# S7G7_footprint_simplified_w_ethernet_v1p.net
KiCad netlist of a schematic drawn in EAGLE
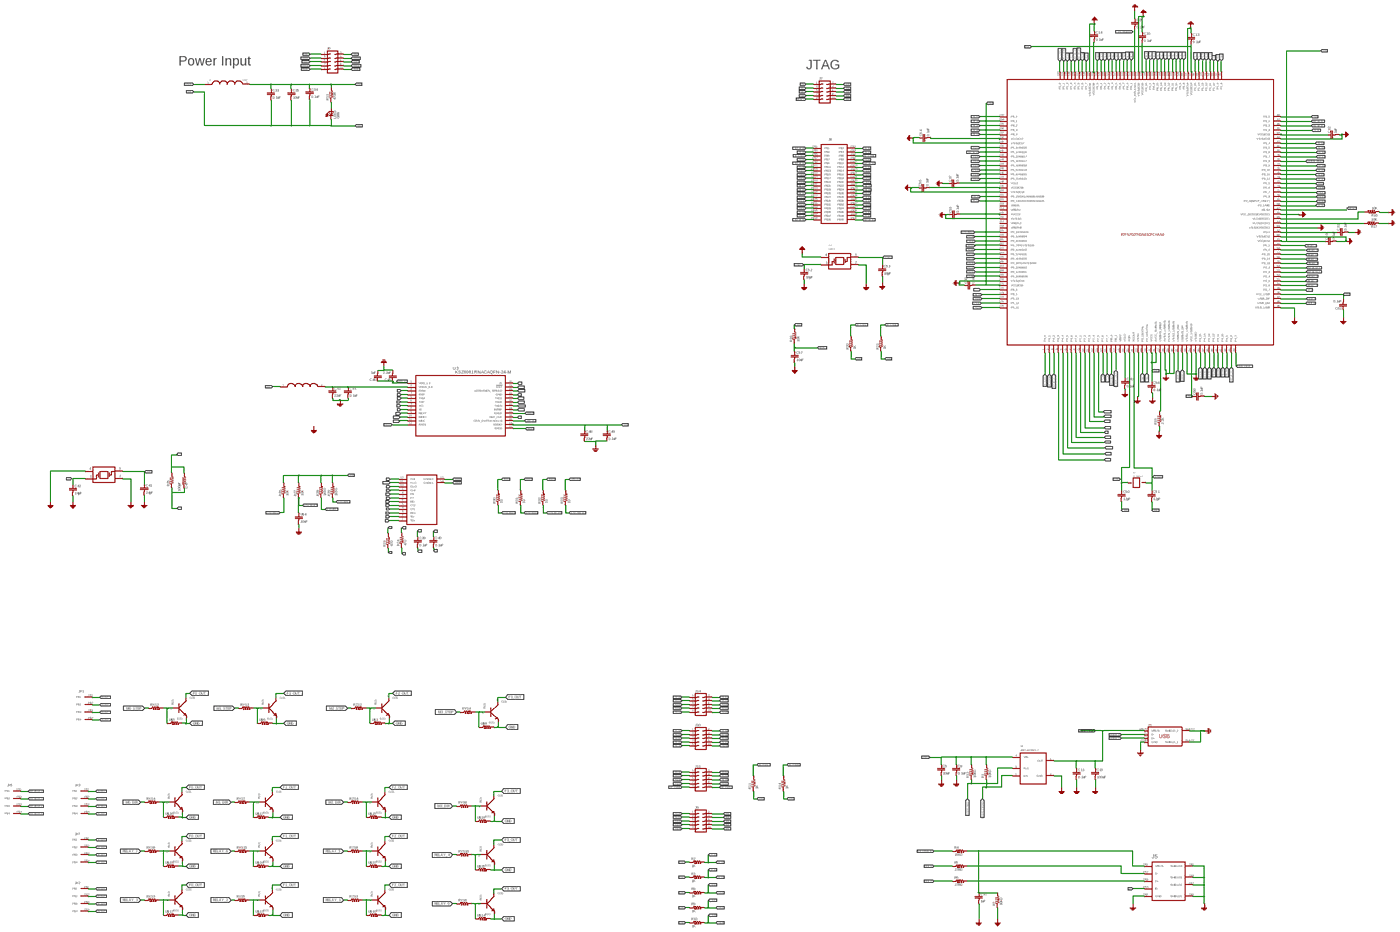
[diagram p0: schematic, sheet 1, overview]
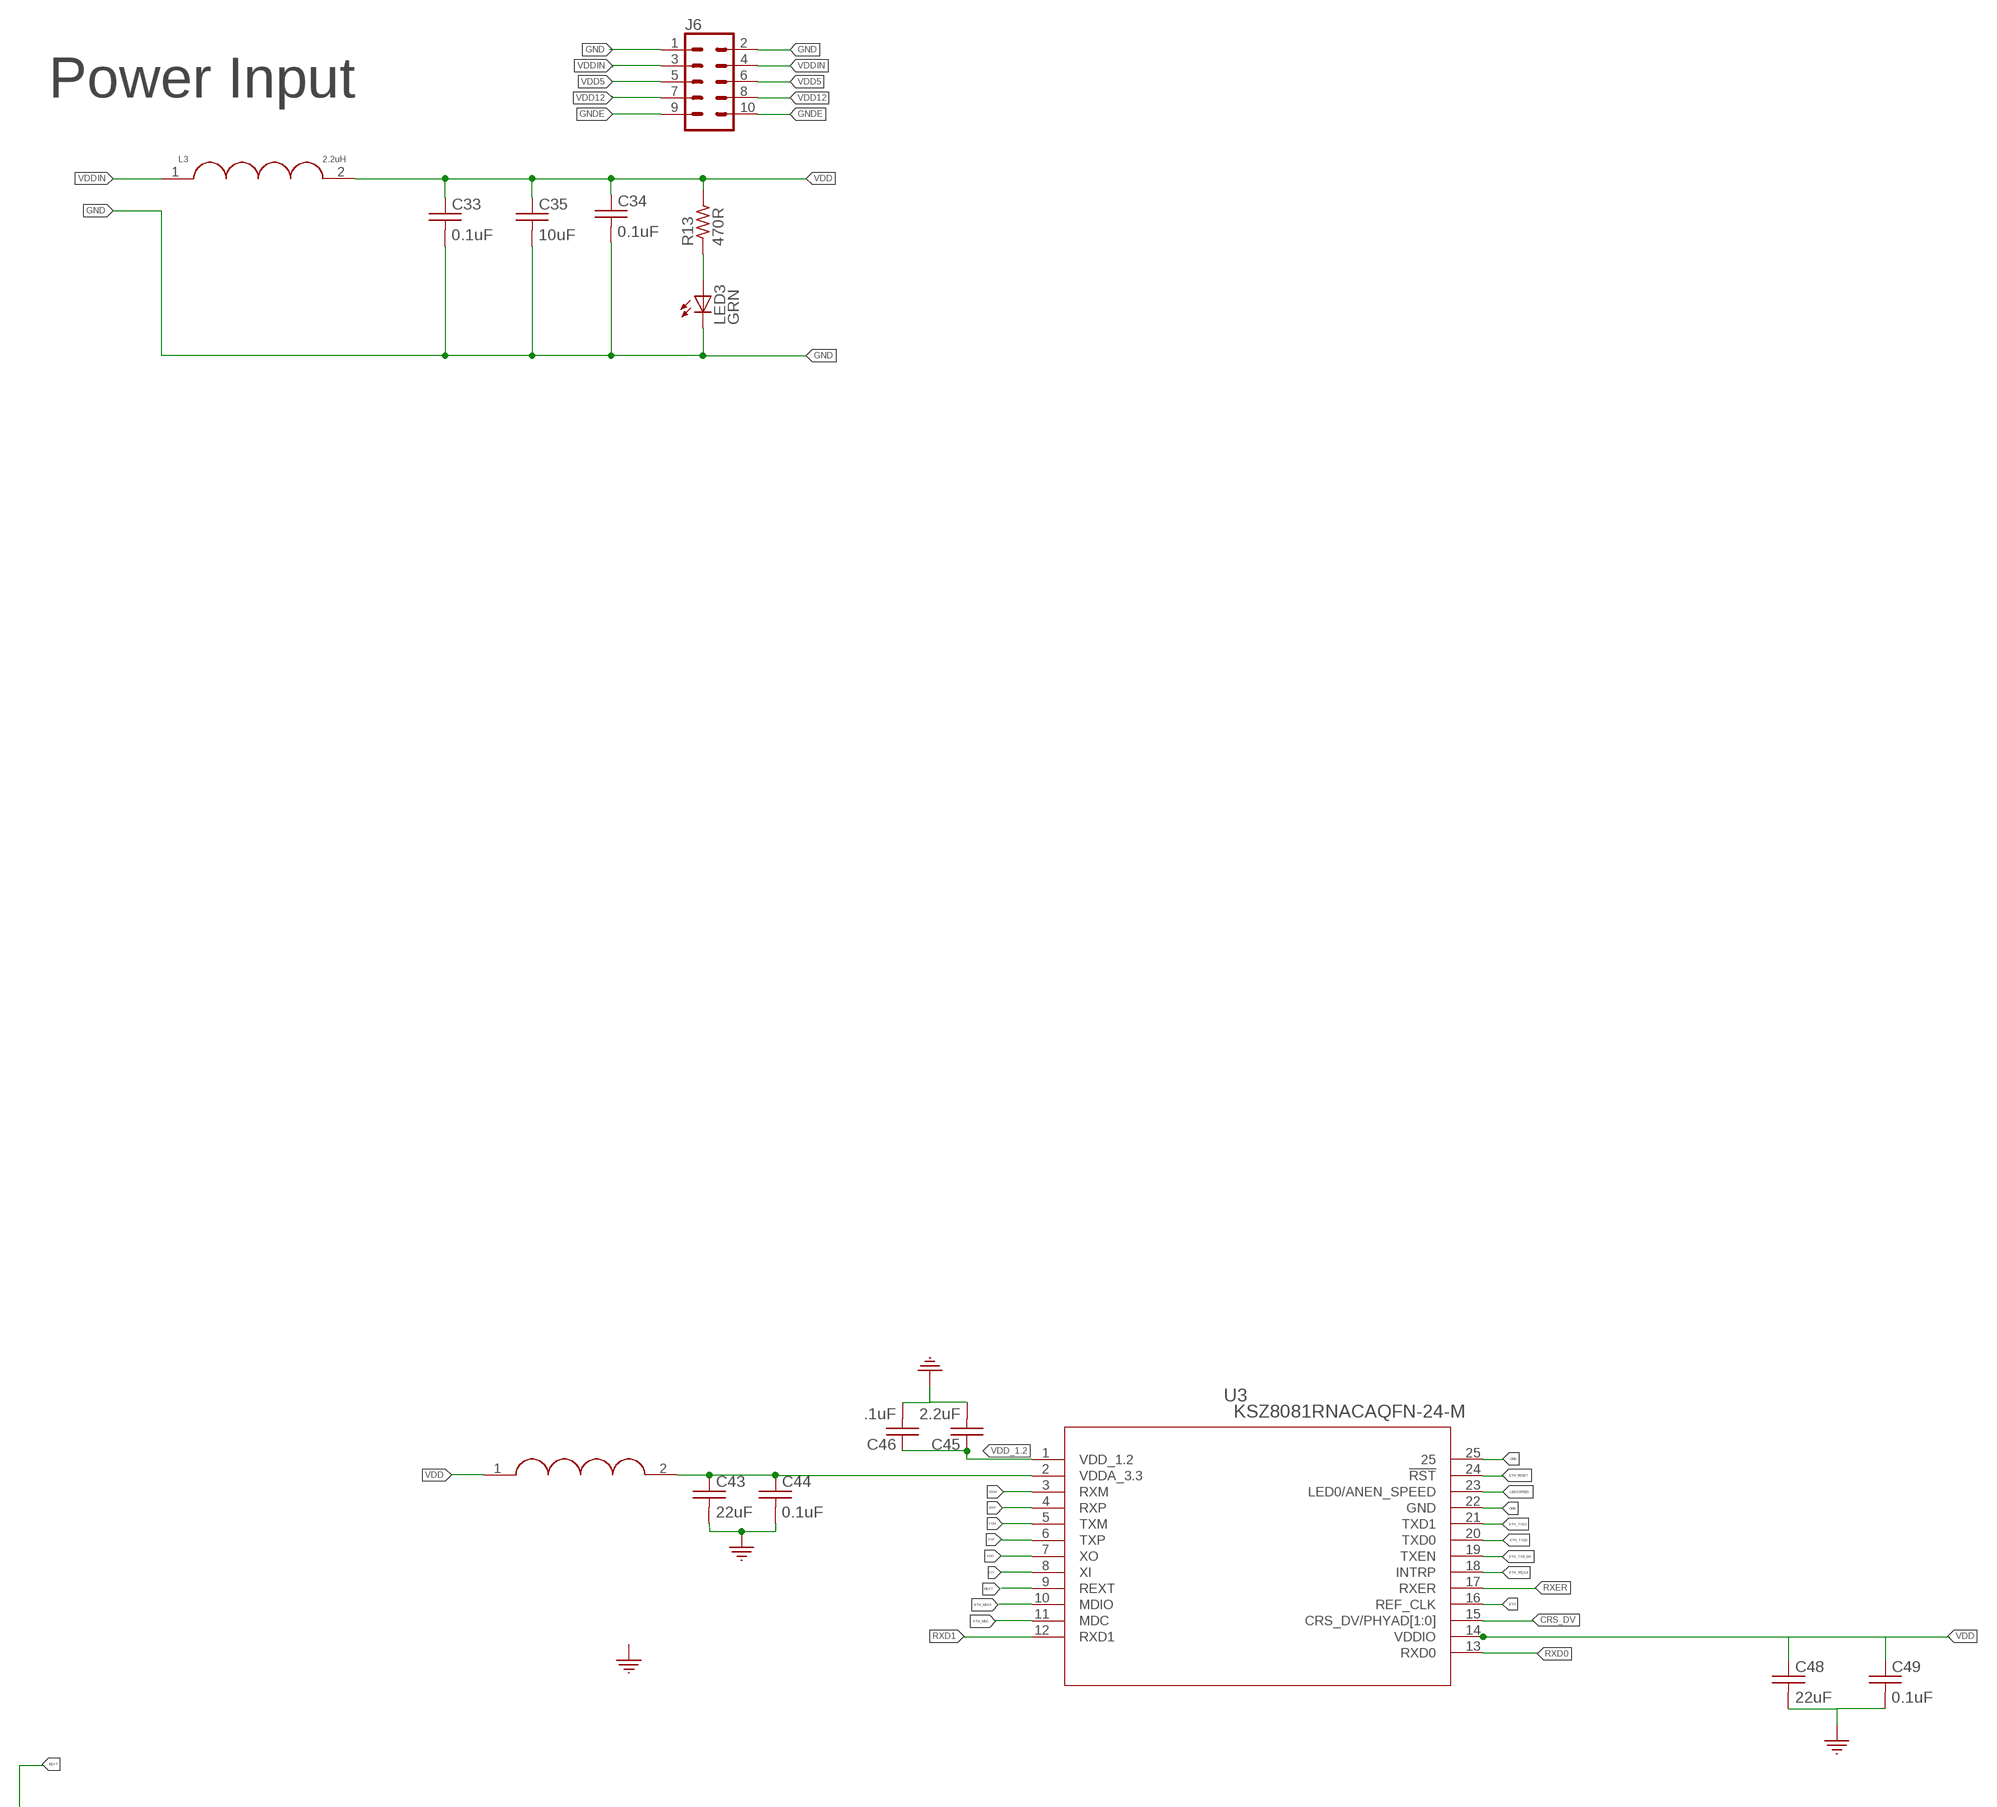
[diagram p1: schematic, sheet 1, part 1 of 4]
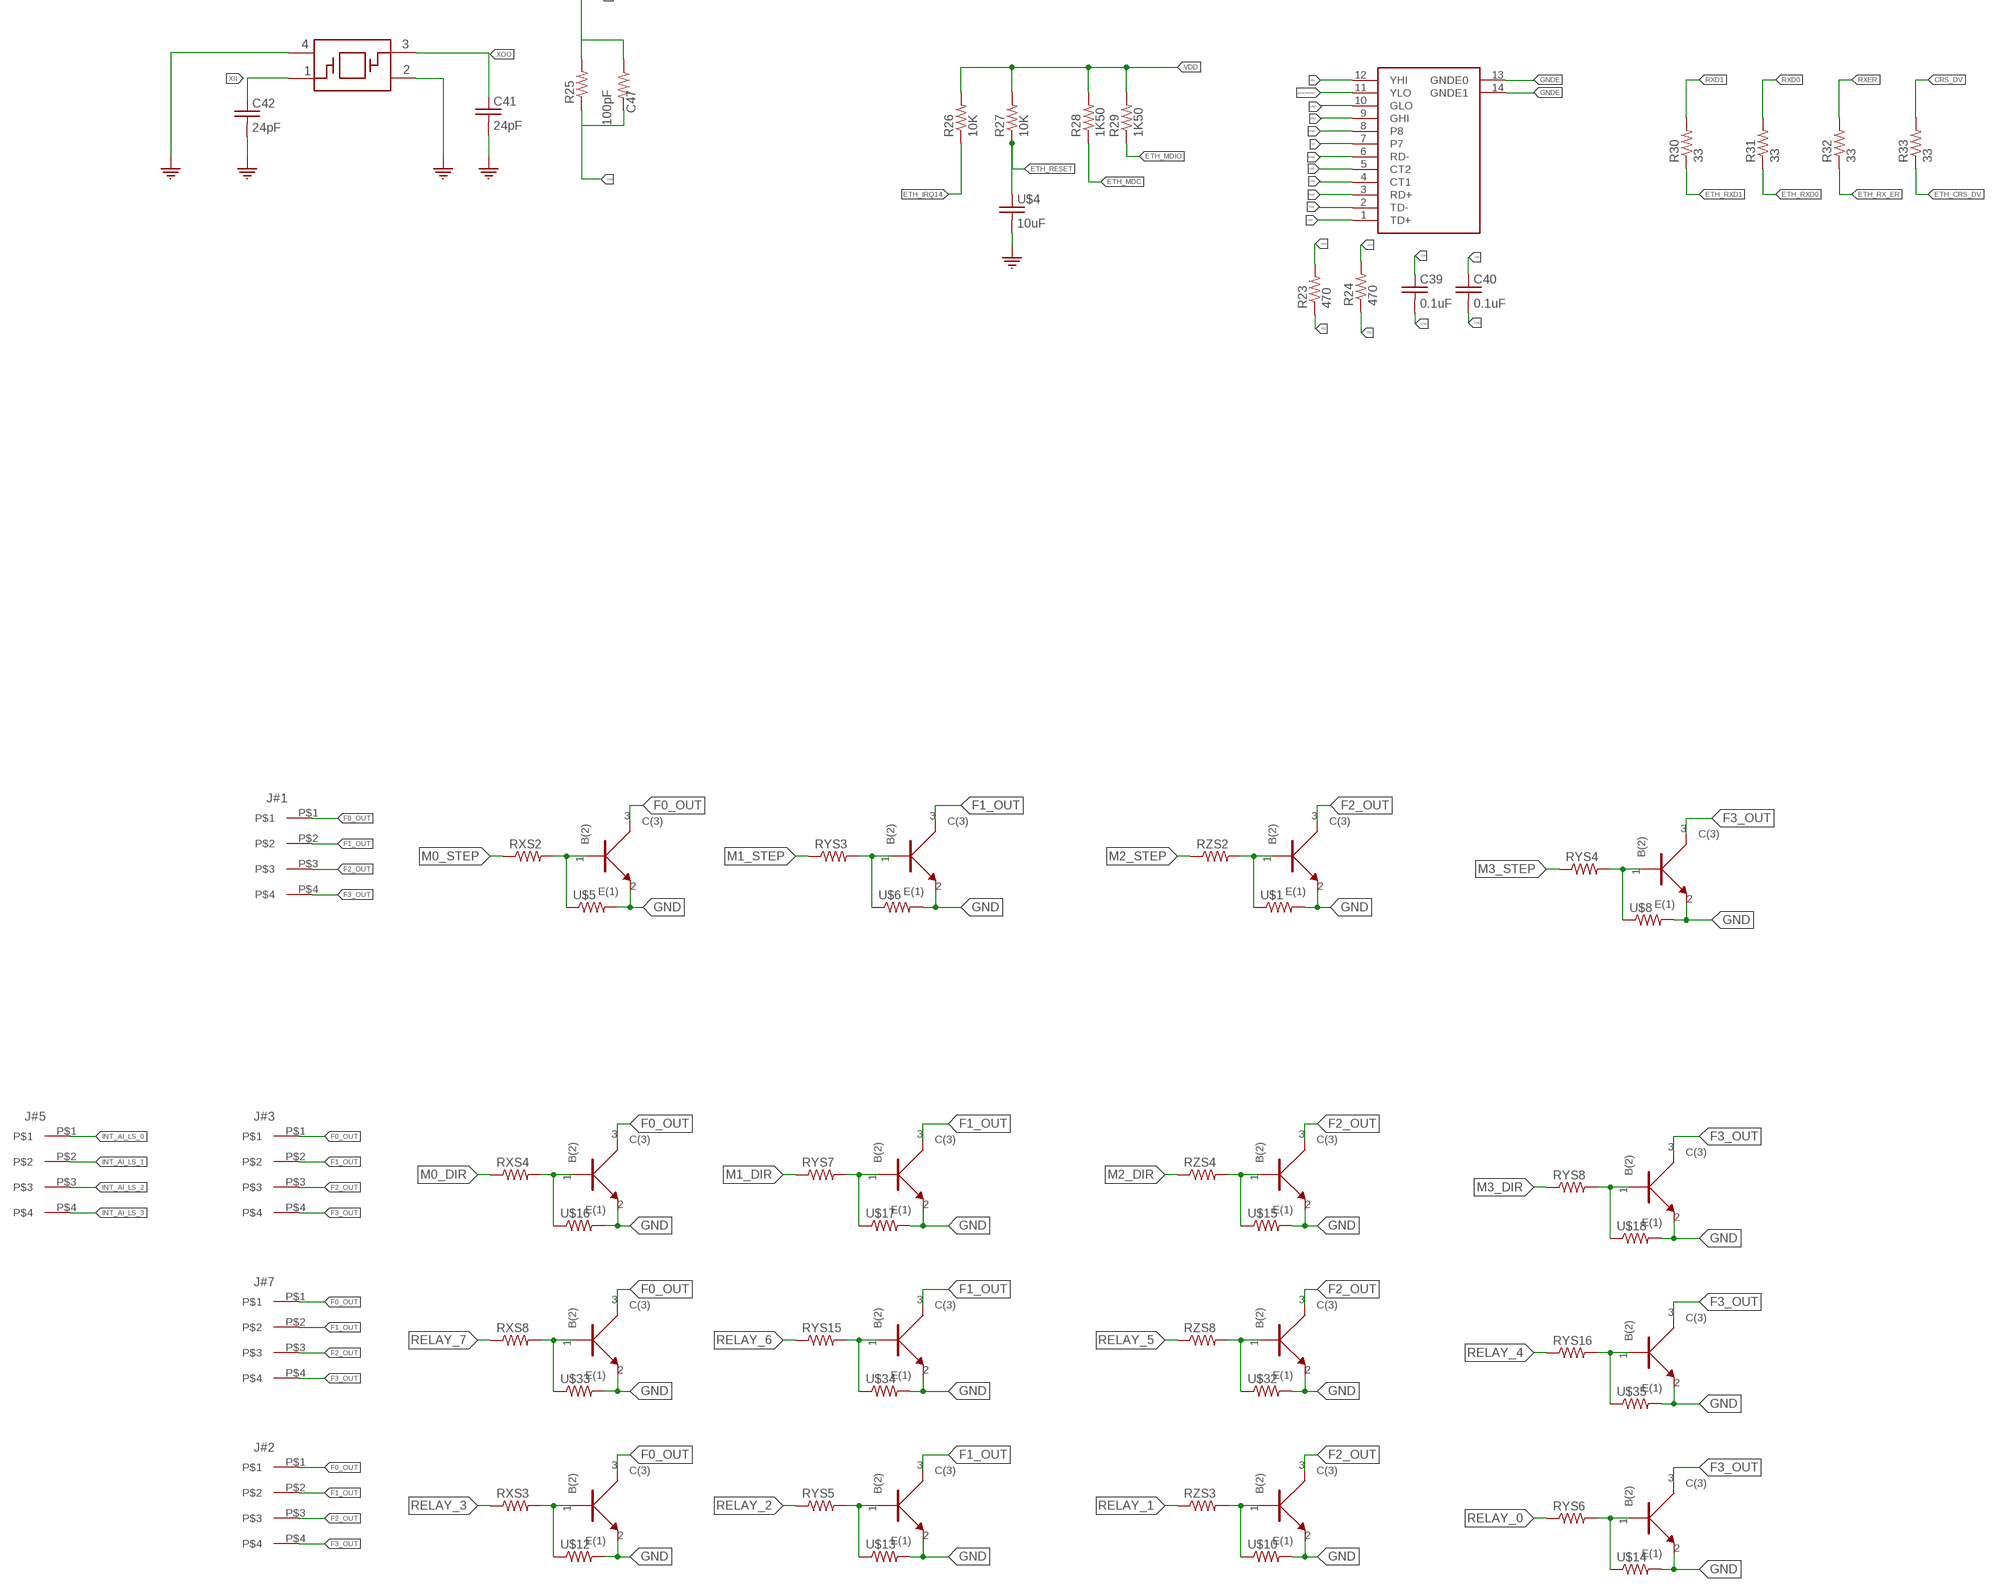
[diagram p2: schematic, sheet 1, part 2 of 4]
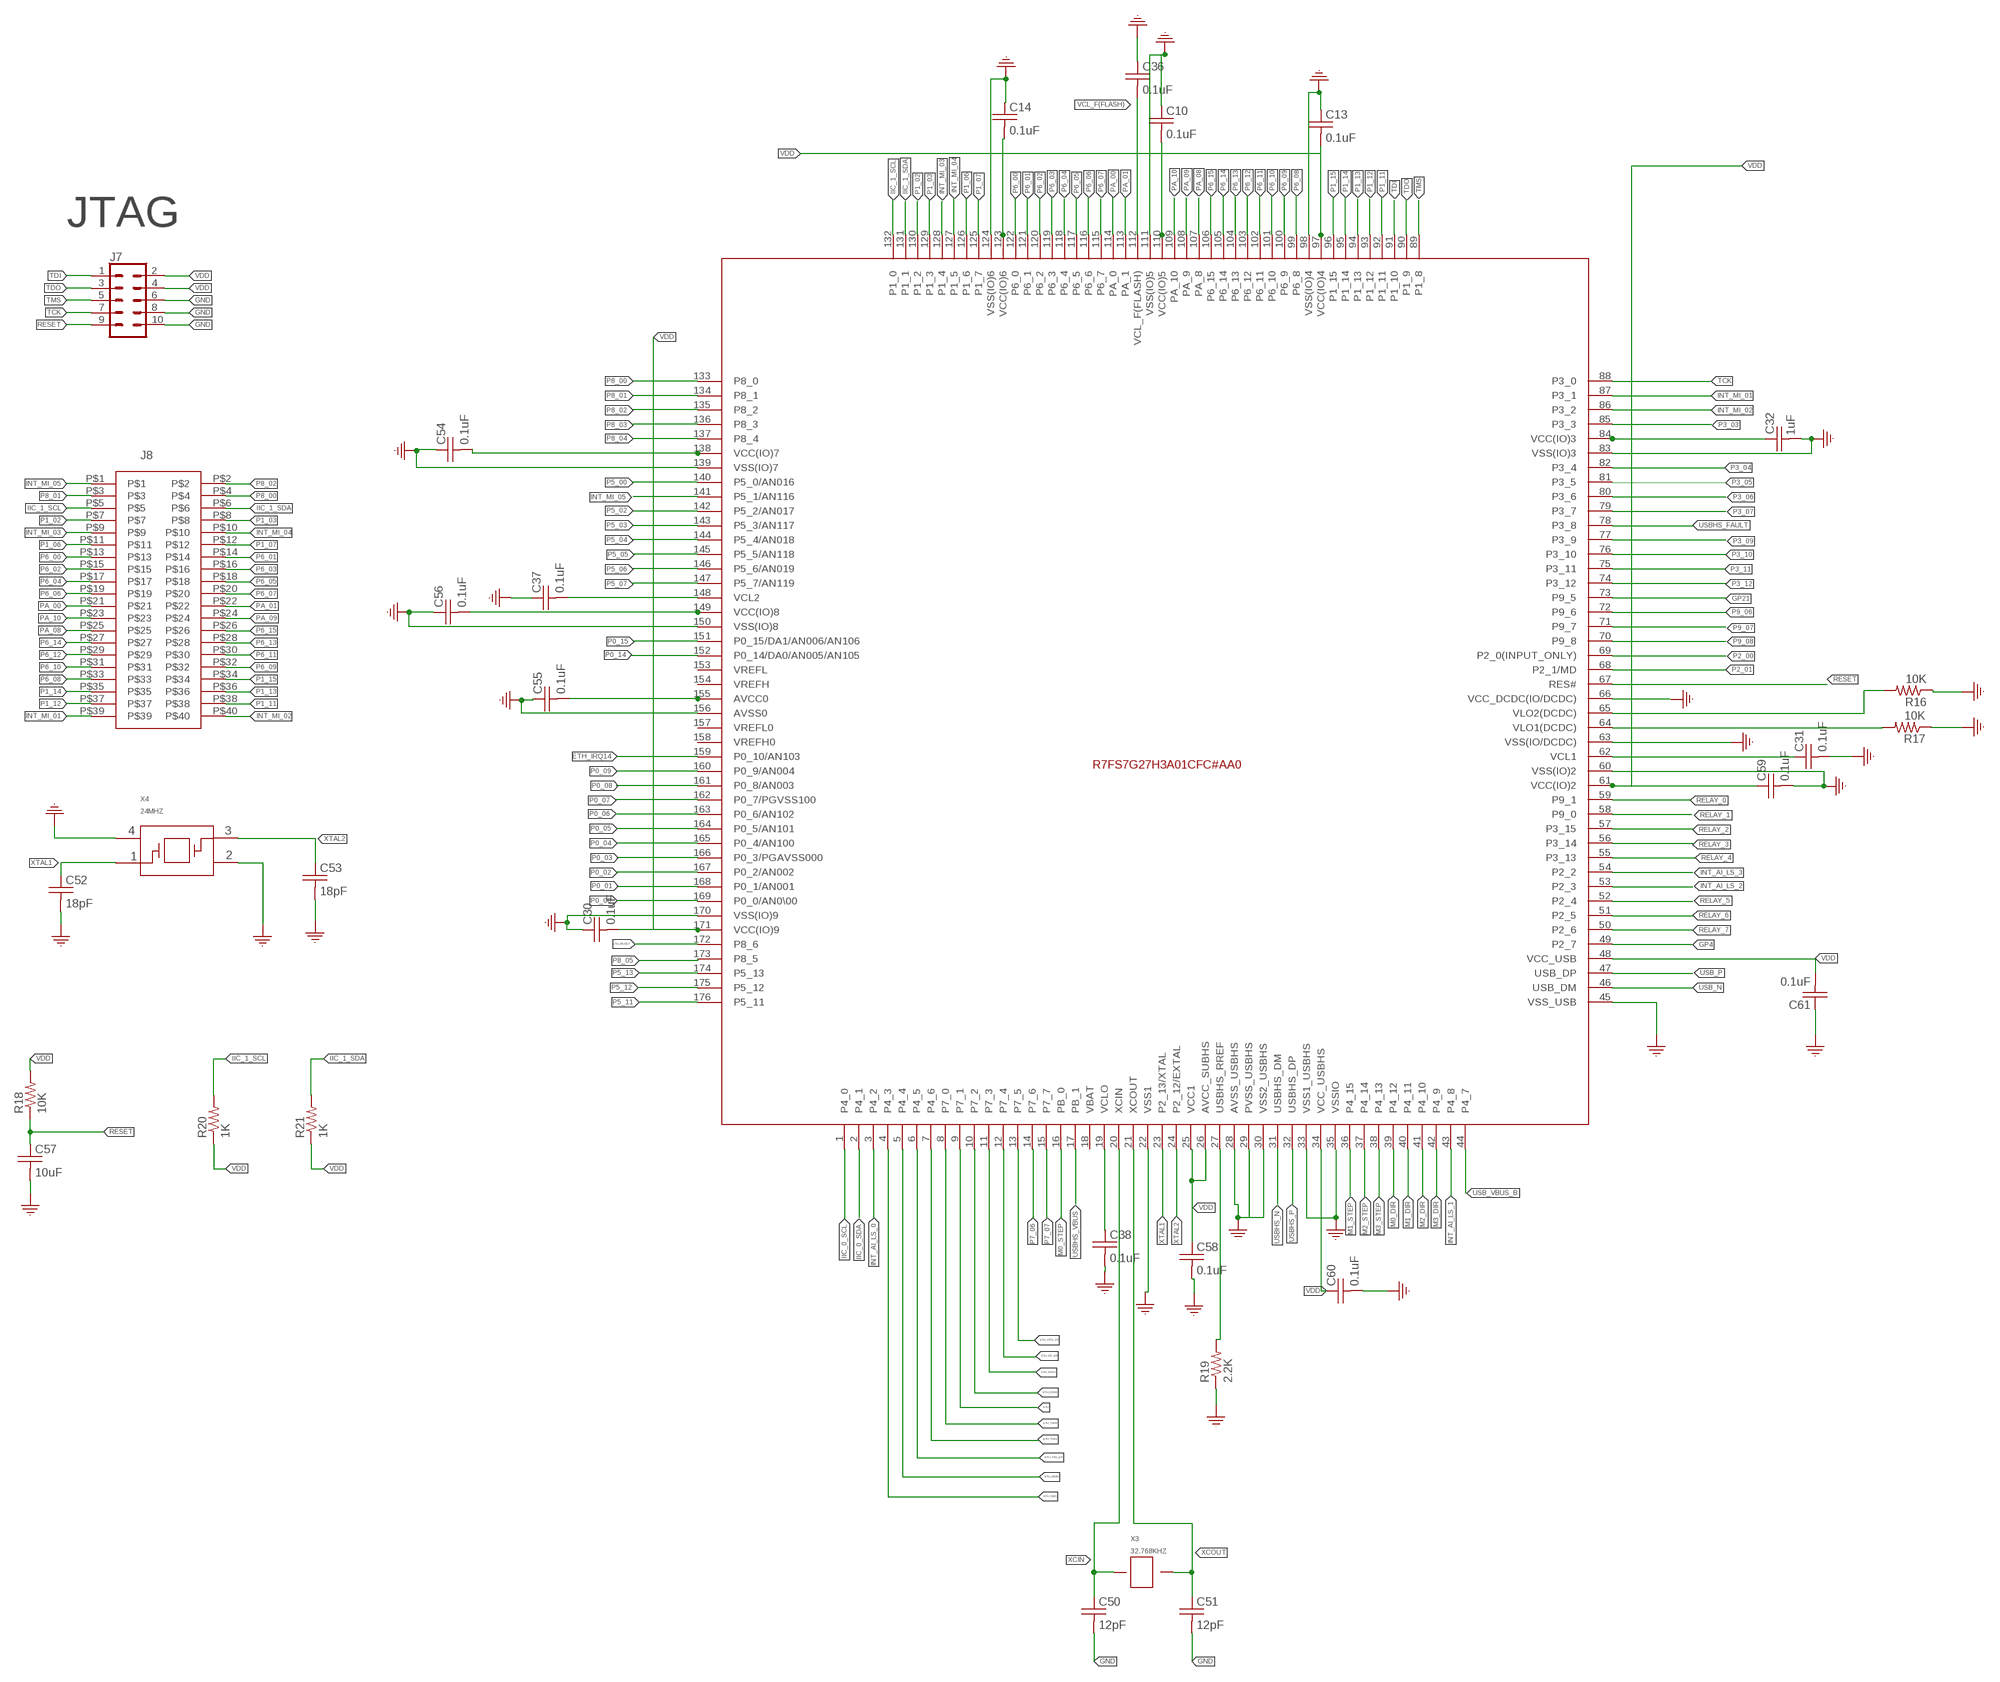
[diagram p3: schematic, sheet 1, part 3 of 4]
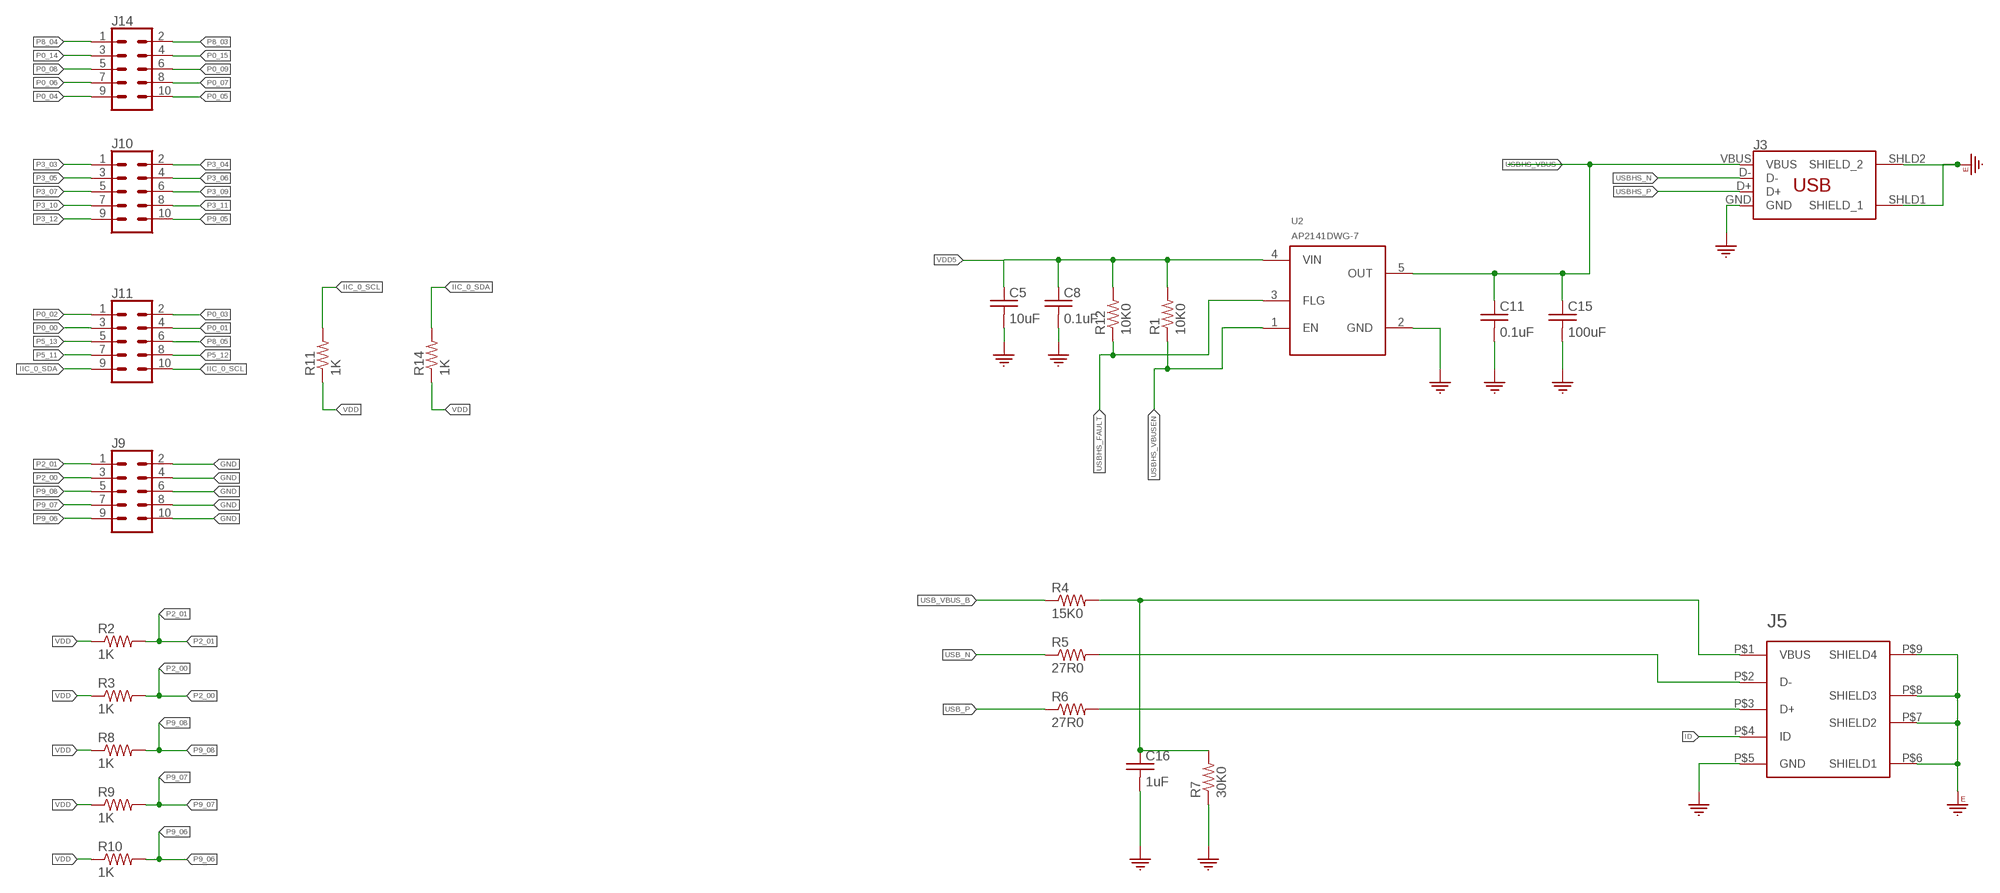
[diagram p4: schematic, sheet 1, part 4 of 4]

(export (version "E")
  (design (tool "Eeschema 10.0.6"))
  (components
    (comp (ref "C5")
      (value "10uF")
      (footprint "eagle-import:0402")
      (libsource (lib "eagle-import") (part "C_0402"))
    )
    (comp (ref "C8")
      (value "0.1uF")
      (footprint "eagle-import:0402")
      (libsource (lib "eagle-import") (part "C_0402"))
    )
    (comp (ref "C10")
      (value "0.1uF")
      (footprint "eagle-import:0402")
      (libsource (lib "eagle-import") (part "C_0402"))
    )
    (comp (ref "C11")
      (value "0.1uF")
      (footprint "eagle-import:0402")
      (libsource (lib "eagle-import") (part "C_0402"))
    )
    (comp (ref "C13")
      (value "0.1uF")
      (footprint "eagle-import:0402")
      (libsource (lib "eagle-import") (part "C_0402"))
    )
    (comp (ref "C14")
      (value "0.1uF")
      (footprint "eagle-import:0402")
      (libsource (lib "eagle-import") (part "C_0402"))
    )
    (comp (ref "C15")
      (value "100uF")
      (footprint "eagle-import:C1210")
      (libsource (lib "eagle-import") (part "C_1210"))
    )
    (comp (ref "C16")
      (value "1uF")
      (footprint "eagle-import:0402")
      (libsource (lib "eagle-import") (part "C_0402"))
    )
    (comp (ref "C30")
      (value "0.1uF")
      (footprint "eagle-import:0402")
      (libsource (lib "eagle-import") (part "C_0402"))
    )
    (comp (ref "C31")
      (value "0.1uF")
      (footprint "eagle-import:0402")
      (libsource (lib "eagle-import") (part "C_0402"))
    )
    (comp (ref "C32")
      (value "1uF")
      (footprint "eagle-import:0402")
      (libsource (lib "eagle-import") (part "C_0402"))
    )
    (comp (ref "C33")
      (value "0.1uF")
      (footprint "eagle-import:0402")
      (libsource (lib "eagle-import") (part "C_0402"))
    )
    (comp (ref "C34")
      (value "0.1uF")
      (footprint "eagle-import:0402")
      (libsource (lib "eagle-import") (part "C_0402"))
    )
    (comp (ref "C35")
      (value "10uF")
      (footprint "eagle-import:0402")
      (libsource (lib "eagle-import") (part "C_0402"))
    )
    (comp (ref "C36")
      (value "0.1uF")
      (footprint "eagle-import:0402")
      (libsource (lib "eagle-import") (part "C_0402"))
    )
    (comp (ref "C37")
      (value "0.1uF")
      (footprint "eagle-import:0402")
      (libsource (lib "eagle-import") (part "C_0402"))
    )
    (comp (ref "C38")
      (value "0.1uF")
      (footprint "eagle-import:0402")
      (libsource (lib "eagle-import") (part "C_0402"))
    )
    (comp (ref "C39")
      (value "0.1uF")
      (footprint "eagle-import:0402")
      (libsource (lib "eagle-import") (part "C_0402"))
    )
    (comp (ref "C40")
      (value "0.1uF")
      (footprint "eagle-import:0402")
      (libsource (lib "eagle-import") (part "C_0402"))
    )
    (comp (ref "C41")
      (value "24pF")
      (footprint "eagle-import:0402")
      (libsource (lib "eagle-import") (part "C_0402"))
    )
    (comp (ref "C42")
      (value "24pF")
      (footprint "eagle-import:0402")
      (libsource (lib "eagle-import") (part "C_0402"))
    )
    (comp (ref "C43")
      (value "22uF")
      (footprint "eagle-import:0603")
      (libsource (lib "eagle-import") (part "C_0603"))
    )
    (comp (ref "C44")
      (value "0.1uF")
      (footprint "eagle-import:0402")
      (libsource (lib "eagle-import") (part "C_0402"))
    )
    (comp (ref "C45")
      (value "2.2uF")
      (footprint "eagle-import:0402")
      (libsource (lib "eagle-import") (part "C_0402"))
    )
    (comp (ref "C46")
      (value ".1uF")
      (footprint "eagle-import:0402")
      (libsource (lib "eagle-import") (part "C_0402"))
    )
    (comp (ref "C47")
      (value "100pF")
      (footprint "eagle-import:0402")
      (libsource (lib "eagle-import") (part "R_0402"))
    )
    (comp (ref "C48")
      (value "22uF")
      (footprint "eagle-import:0603")
      (libsource (lib "eagle-import") (part "C_0603"))
    )
    (comp (ref "C49")
      (value "0.1uF")
      (footprint "eagle-import:0402")
      (libsource (lib "eagle-import") (part "C_0402"))
    )
    (comp (ref "C50")
      (value "12pF")
      (footprint "eagle-import:0402")
      (libsource (lib "eagle-import") (part "C_0402"))
    )
    (comp (ref "C51")
      (value "12pF")
      (footprint "eagle-import:0402")
      (libsource (lib "eagle-import") (part "C_0402"))
    )
    (comp (ref "C52")
      (value "18pF")
      (footprint "eagle-import:0402")
      (libsource (lib "eagle-import") (part "C_0402"))
    )
    (comp (ref "C53")
      (value "18pF")
      (footprint "eagle-import:0402")
      (libsource (lib "eagle-import") (part "C_0402"))
    )
    (comp (ref "C54")
      (value "0.1uF")
      (footprint "eagle-import:0402")
      (libsource (lib "eagle-import") (part "C_0402"))
    )
    (comp (ref "C55")
      (value "0.1uF")
      (footprint "eagle-import:0402")
      (libsource (lib "eagle-import") (part "C_0402"))
    )
    (comp (ref "C56")
      (value "0.1uF")
      (footprint "eagle-import:0402")
      (libsource (lib "eagle-import") (part "C_0402"))
    )
    (comp (ref "C57")
      (value "10uF")
      (footprint "eagle-import:0402")
      (libsource (lib "eagle-import") (part "C_0402"))
    )
    (comp (ref "C58")
      (value "0.1uF")
      (footprint "eagle-import:0402")
      (libsource (lib "eagle-import") (part "C_0402"))
    )
    (comp (ref "C59")
      (value "0.1uF")
      (footprint "eagle-import:0402")
      (libsource (lib "eagle-import") (part "C_0402"))
    )
    (comp (ref "C60")
      (value "0.1uF")
      (footprint "eagle-import:0402")
      (libsource (lib "eagle-import") (part "C_0402"))
    )
    (comp (ref "C61")
      (value "0.1uF")
      (footprint "eagle-import:0402")
      (libsource (lib "eagle-import") (part "C_0402"))
    )
    (comp (ref "FB2/2")
      (value "FB_0805_120_OHM")
      (footprint "eagle-import:0805")
      (libsource (lib "eagle-import") (part "FB_0805_120_OHM"))
    )
    (comp (ref "J#1")
      (value "3.81MM_1_X_4_RT_ANGLE_PLUG_HEADER")
      (footprint "eagle-import:1X4_3.81MM_PITCH")
      (libsource (lib "eagle-import") (part "3.81MM_1_X_4_RT_ANGLE_PLUG_HEADER"))
    )
    (comp (ref "J#2")
      (value "3.81MM_1_X_4_RT_ANGLE_PLUG_HEADER")
      (footprint "eagle-import:1X4_3.81MM_PITCH")
      (libsource (lib "eagle-import") (part "3.81MM_1_X_4_RT_ANGLE_PLUG_HEADER"))
    )
    (comp (ref "J#3")
      (value "3.81MM_1_X_4_RT_ANGLE_PLUG_HEADER")
      (footprint "eagle-import:1X4_3.81MM_PITCH")
      (libsource (lib "eagle-import") (part "3.81MM_1_X_4_RT_ANGLE_PLUG_HEADER"))
    )
    (comp (ref "J#5")
      (value "3.81MM_1_X_4_RT_ANGLE_PLUG_HEADER")
      (footprint "eagle-import:1X4_3.81MM_PITCH")
      (libsource (lib "eagle-import") (part "3.81MM_1_X_4_RT_ANGLE_PLUG_HEADER"))
    )
    (comp (ref "J#7")
      (value "3.81MM_1_X_4_RT_ANGLE_PLUG_HEADER")
      (footprint "eagle-import:1X4_3.81MM_PITCH")
      (libsource (lib "eagle-import") (part "3.81MM_1_X_4_RT_ANGLE_PLUG_HEADER"))
    )
    (comp (ref "J3")
      (value "USB_A")
      (footprint "eagle-import:USB_A_SMT")
      (libsource (lib "eagle-import") (part "USB_A"))
    )
    (comp (ref "J5")
      (value "USB_MICRO-B")
      (footprint "eagle-import:USB_MICRO-B")
      (libsource (lib "eagle-import") (part "USB_MICRO-B"))
    )
    (comp (ref "J6")
      (value "CONN_05X2PTH")
      (footprint "eagle-import:2X5")
      (libsource (lib "eagle-import") (part "CONN_05X2PTH"))
    )
    (comp (ref "J7")
      (value "CONN_05X2PTH")
      (footprint "eagle-import:2X5")
      (libsource (lib "eagle-import") (part "CONN_05X2PTH"))
    )
    (comp (ref "J8")
      (value "HEADER_2_X_20_GENERIC")
      (footprint "eagle-import:HEADER_2_X_20_.1_INCH")
      (libsource (lib "eagle-import") (part "HEADER_2_X_20_GENERIC"))
    )
    (comp (ref "J9")
      (value "CONN_05X2SHD_SMD")
      (footprint "eagle-import:2X5-SHROUDED_SMD")
      (libsource (lib "eagle-import") (part "CONN_05X2SHD_SMD"))
    )
    (comp (ref "J10")
      (value "CONN_05X2NO_SILK")
      (footprint "eagle-import:2X5_NOSILK")
      (libsource (lib "eagle-import") (part "CONN_05X2NO_SILK"))
    )
    (comp (ref "J11")
      (value "CONN_05X2NO_SILK")
      (footprint "eagle-import:2X5_NOSILK")
      (libsource (lib "eagle-import") (part "CONN_05X2NO_SILK"))
    )
    (comp (ref "J14")
      (value "CONN_05X2NO_SILK")
      (footprint "eagle-import:2X5_NOSILK")
      (libsource (lib "eagle-import") (part "CONN_05X2NO_SILK"))
    )
    (comp (ref "L3")
      (value "2.2uH")
      (footprint "eagle-import:1008_(2520_METRIC)")
      (libsource (lib "eagle-import") (part "INDUCTOR_1008_2.2_MH_1.3A"))
    )
    (comp (ref "LED3")
      (value "LED_0805_GREEN")
      (footprint "eagle-import:LED_0805_GREEN")
      (libsource (lib "eagle-import") (part "LED_0805_GREEN"))
    )
    (comp (ref "R1")
      (value "10K0")
      (footprint "eagle-import:0402")
      (libsource (lib "eagle-import") (part "R_0402"))
    )
    (comp (ref "R2")
      (value "1K")
      (footprint "eagle-import:0402")
      (libsource (lib "eagle-import") (part "R_0402"))
    )
    (comp (ref "R3")
      (value "1K")
      (footprint "eagle-import:0402")
      (libsource (lib "eagle-import") (part "R_0402"))
    )
    (comp (ref "R4")
      (value "15K0")
      (footprint "eagle-import:0402")
      (libsource (lib "eagle-import") (part "R_0402"))
    )
    (comp (ref "R5")
      (value "27R0")
      (footprint "eagle-import:0402")
      (libsource (lib "eagle-import") (part "R_0402"))
    )
    (comp (ref "R6")
      (value "27R0")
      (footprint "eagle-import:0402")
      (libsource (lib "eagle-import") (part "R_0402"))
    )
    (comp (ref "R7")
      (value "30K0")
      (footprint "eagle-import:0402")
      (libsource (lib "eagle-import") (part "R_0402"))
    )
    (comp (ref "R8")
      (value "1K")
      (footprint "eagle-import:0402")
      (libsource (lib "eagle-import") (part "R_0402"))
    )
    (comp (ref "R9")
      (value "1K")
      (footprint "eagle-import:0402")
      (libsource (lib "eagle-import") (part "R_0402"))
    )
    (comp (ref "R10")
      (value "1K")
      (footprint "eagle-import:0402")
      (libsource (lib "eagle-import") (part "R_0402"))
    )
    (comp (ref "R11")
      (value "1K")
      (footprint "eagle-import:0402")
      (libsource (lib "eagle-import") (part "R_0402"))
    )
    (comp (ref "R12")
      (value "10K0")
      (footprint "eagle-import:0402")
      (libsource (lib "eagle-import") (part "R_0402"))
    )
    (comp (ref "R13")
      (value "470R")
      (footprint "eagle-import:0402")
      (libsource (lib "eagle-import") (part "R_0402"))
    )
    (comp (ref "R14")
      (value "1K")
      (footprint "eagle-import:0402")
      (libsource (lib "eagle-import") (part "R_0402"))
    )
    (comp (ref "R16")
      (value "10K")
      (footprint "eagle-import:0402")
      (libsource (lib "eagle-import") (part "R_0402"))
    )
    (comp (ref "R17")
      (value "10K")
      (footprint "eagle-import:0402")
      (libsource (lib "eagle-import") (part "R_0402"))
    )
    (comp (ref "R18")
      (value "10K")
      (footprint "eagle-import:0402")
      (libsource (lib "eagle-import") (part "R_0402"))
    )
    (comp (ref "R19")
      (value "2.2K")
      (footprint "eagle-import:0402")
      (libsource (lib "eagle-import") (part "R_0402"))
    )
    (comp (ref "R20")
      (value "1K")
      (footprint "eagle-import:0402")
      (libsource (lib "eagle-import") (part "R_0402"))
    )
    (comp (ref "R21")
      (value "1K")
      (footprint "eagle-import:0402")
      (libsource (lib "eagle-import") (part "R_0402"))
    )
    (comp (ref "R23")
      (value "470")
      (footprint "eagle-import:0402")
      (libsource (lib "eagle-import") (part "R_0402"))
    )
    (comp (ref "R24")
      (value "470")
      (footprint "eagle-import:0402")
      (libsource (lib "eagle-import") (part "R_0402"))
    )
    (comp (ref "R25")
      (value "6k49")
      (footprint "eagle-import:0402")
      (libsource (lib "eagle-import") (part "R_0402"))
    )
    (comp (ref "R26")
      (value "10K")
      (footprint "eagle-import:0402")
      (libsource (lib "eagle-import") (part "R_0402"))
    )
    (comp (ref "R27")
      (value "10K")
      (footprint "eagle-import:0402")
      (libsource (lib "eagle-import") (part "R_0402"))
    )
    (comp (ref "R28")
      (value "1K50")
      (footprint "eagle-import:0402")
      (libsource (lib "eagle-import") (part "R_0402"))
    )
    (comp (ref "R29")
      (value "1K50")
      (footprint "eagle-import:0402")
      (libsource (lib "eagle-import") (part "R_0402"))
    )
    (comp (ref "R30")
      (value "33")
      (footprint "eagle-import:0402")
      (libsource (lib "eagle-import") (part "R_0402"))
    )
    (comp (ref "R31")
      (value "33")
      (footprint "eagle-import:0402")
      (libsource (lib "eagle-import") (part "R_0402"))
    )
    (comp (ref "R32")
      (value "33")
      (footprint "eagle-import:0402")
      (libsource (lib "eagle-import") (part "R_0402"))
    )
    (comp (ref "R33")
      (value "33")
      (footprint "eagle-import:0402")
      (libsource (lib "eagle-import") (part "R_0402"))
    )
    (comp (ref "RXS2")
      (value "R_0402")
      (footprint "eagle-import:0402")
      (libsource (lib "eagle-import") (part "R_0402"))
    )
    (comp (ref "RXS3")
      (value "R_0402")
      (footprint "eagle-import:0402")
      (libsource (lib "eagle-import") (part "R_0402"))
    )
    (comp (ref "RXS4")
      (value "R_0402")
      (footprint "eagle-import:0402")
      (libsource (lib "eagle-import") (part "R_0402"))
    )
    (comp (ref "RXS8")
      (value "R_0402")
      (footprint "eagle-import:0402")
      (libsource (lib "eagle-import") (part "R_0402"))
    )
    (comp (ref "RYS3")
      (value "R_0402")
      (footprint "eagle-import:0402")
      (libsource (lib "eagle-import") (part "R_0402"))
    )
    (comp (ref "RYS4")
      (value "R_0402")
      (footprint "eagle-import:0402")
      (libsource (lib "eagle-import") (part "R_0402"))
    )
    (comp (ref "RYS5")
      (value "R_0402")
      (footprint "eagle-import:0402")
      (libsource (lib "eagle-import") (part "R_0402"))
    )
    (comp (ref "RYS6")
      (value "R_0402")
      (footprint "eagle-import:0402")
      (libsource (lib "eagle-import") (part "R_0402"))
    )
    (comp (ref "RYS7")
      (value "R_0402")
      (footprint "eagle-import:0402")
      (libsource (lib "eagle-import") (part "R_0402"))
    )
    (comp (ref "RYS8")
      (value "R_0402")
      (footprint "eagle-import:0402")
      (libsource (lib "eagle-import") (part "R_0402"))
    )
    (comp (ref "RYS15")
      (value "R_0402")
      (footprint "eagle-import:0402")
      (libsource (lib "eagle-import") (part "R_0402"))
    )
    (comp (ref "RYS16")
      (value "R_0402")
      (footprint "eagle-import:0402")
      (libsource (lib "eagle-import") (part "R_0402"))
    )
    (comp (ref "RZS2")
      (value "R_0402")
      (footprint "eagle-import:0402")
      (libsource (lib "eagle-import") (part "R_0402"))
    )
    (comp (ref "RZS3")
      (value "R_0402")
      (footprint "eagle-import:0402")
      (libsource (lib "eagle-import") (part "R_0402"))
    )
    (comp (ref "RZS4")
      (value "R_0402")
      (footprint "eagle-import:0402")
      (libsource (lib "eagle-import") (part "R_0402"))
    )
    (comp (ref "RZS8")
      (value "R_0402")
      (footprint "eagle-import:0402")
      (libsource (lib "eagle-import") (part "R_0402"))
    )
    (comp (ref "U$1")
      (value "R_0402")
      (footprint "eagle-import:0402")
      (libsource (lib "eagle-import") (part "R_0402"))
    )
    (comp (ref "U$2")
      (value "RJ45_WITH_ELEC")
      (footprint "eagle-import:RJ45_TH_ELEC")
      (libsource (lib "eagle-import") (part "RJ45_WITH_ELEC"))
    )
    (comp (ref "U$3")
      (value "XTAL_25_MHZ")
      (footprint "eagle-import:SMD_3225")
      (libsource (lib "eagle-import") (part "XTAL_25_MHZ"))
    )
    (comp (ref "U$4")
      (value "10uF")
      (footprint "eagle-import:0402")
      (libsource (lib "eagle-import") (part "C_0402"))
    )
    (comp (ref "U$5")
      (value "R_0402")
      (footprint "eagle-import:0402")
      (libsource (lib "eagle-import") (part "R_0402"))
    )
    (comp (ref "U$6")
      (value "R_0402")
      (footprint "eagle-import:0402")
      (libsource (lib "eagle-import") (part "R_0402"))
    )
    (comp (ref "U$8")
      (value "R_0402")
      (footprint "eagle-import:0402")
      (libsource (lib "eagle-import") (part "R_0402"))
    )
    (comp (ref "U$10")
      (value "R_0402")
      (footprint "eagle-import:0402")
      (libsource (lib "eagle-import") (part "R_0402"))
    )
    (comp (ref "U$12")
      (value "R_0402")
      (footprint "eagle-import:0402")
      (libsource (lib "eagle-import") (part "R_0402"))
    )
    (comp (ref "U$13")
      (value "R_0402")
      (footprint "eagle-import:0402")
      (libsource (lib "eagle-import") (part "R_0402"))
    )
    (comp (ref "U$14")
      (value "R_0402")
      (footprint "eagle-import:0402")
      (libsource (lib "eagle-import") (part "R_0402"))
    )
    (comp (ref "U$15")
      (value "R_0402")
      (footprint "eagle-import:0402")
      (libsource (lib "eagle-import") (part "R_0402"))
    )
    (comp (ref "U$16")
      (value "R_0402")
      (footprint "eagle-import:0402")
      (libsource (lib "eagle-import") (part "R_0402"))
    )
    (comp (ref "U$17")
      (value "R_0402")
      (footprint "eagle-import:0402")
      (libsource (lib "eagle-import") (part "R_0402"))
    )
    (comp (ref "U$18")
      (value "R_0402")
      (footprint "eagle-import:0402")
      (libsource (lib "eagle-import") (part "R_0402"))
    )
    (comp (ref "U$32")
      (value "R_0402")
      (footprint "eagle-import:0402")
      (libsource (lib "eagle-import") (part "R_0402"))
    )
    (comp (ref "U$33")
      (value "R_0402")
      (footprint "eagle-import:0402")
      (libsource (lib "eagle-import") (part "R_0402"))
    )
    (comp (ref "U$34")
      (value "R_0402")
      (footprint "eagle-import:0402")
      (libsource (lib "eagle-import") (part "R_0402"))
    )
    (comp (ref "U$35")
      (value "R_0402")
      (footprint "eagle-import:0402")
      (libsource (lib "eagle-import") (part "R_0402"))
    )
    (comp (ref "U2")
      (value "AP2141DWG-5")
      (footprint "eagle-import:SOT-23-5")
      (libsource (lib "eagle-import") (part "AP2141DWG-5"))
    )
    (comp (ref "U3")
      (value "KSZ8081RNACAQFN-24-M")
      (footprint "eagle-import:QFN-24-M")
      (fields (field (name "MANUFACTURER_PART_NUMBER") "KSZ8081RNACA"))
      (libsource (lib "eagle-import") (part "KSZ8081RNACAQFN-24-M"))
    )
    (comp (ref "U4")
      (value "S7G2_X_176")
      (footprint "eagle-import:LQFP176_24X24")
      (libsource (lib "eagle-import") (part "S7G2_X_176"))
    )
    (comp (ref "U7")
      (value "BC846BW")
      (footprint "eagle-import:SOT323")
      (libsource (lib "eagle-import") (part "BC846BW"))
    )
    (comp (ref "U8")
      (value "BC846BW")
      (footprint "eagle-import:SOT323")
      (libsource (lib "eagle-import") (part "BC846BW"))
    )
    (comp (ref "U9")
      (value "BC846BW")
      (footprint "eagle-import:SOT323")
      (libsource (lib "eagle-import") (part "BC846BW"))
    )
    (comp (ref "U10")
      (value "BC846BW")
      (footprint "eagle-import:SOT323")
      (libsource (lib "eagle-import") (part "BC846BW"))
    )
    (comp (ref "U12")
      (value "BC846BW")
      (footprint "eagle-import:SOT323")
      (libsource (lib "eagle-import") (part "BC846BW"))
    )
    (comp (ref "U13")
      (value "BC846BW")
      (footprint "eagle-import:SOT323")
      (libsource (lib "eagle-import") (part "BC846BW"))
    )
    (comp (ref "U14")
      (value "BC846BW")
      (footprint "eagle-import:SOT323")
      (libsource (lib "eagle-import") (part "BC846BW"))
    )
    (comp (ref "U15")
      (value "BC846BW")
      (footprint "eagle-import:SOT323")
      (libsource (lib "eagle-import") (part "BC846BW"))
    )
    (comp (ref "U16")
      (value "BC846BW")
      (footprint "eagle-import:SOT323")
      (libsource (lib "eagle-import") (part "BC846BW"))
    )
    (comp (ref "U17")
      (value "BC846BW")
      (footprint "eagle-import:SOT323")
      (libsource (lib "eagle-import") (part "BC846BW"))
    )
    (comp (ref "U18")
      (value "BC846BW")
      (footprint "eagle-import:SOT323")
      (libsource (lib "eagle-import") (part "BC846BW"))
    )
    (comp (ref "U19")
      (value "BC846BW")
      (footprint "eagle-import:SOT323")
      (libsource (lib "eagle-import") (part "BC846BW"))
    )
    (comp (ref "U32")
      (value "BC846BW")
      (footprint "eagle-import:SOT323")
      (libsource (lib "eagle-import") (part "BC846BW"))
    )
    (comp (ref "U33")
      (value "BC846BW")
      (footprint "eagle-import:SOT323")
      (libsource (lib "eagle-import") (part "BC846BW"))
    )
    (comp (ref "U34")
      (value "BC846BW")
      (footprint "eagle-import:SOT323")
      (libsource (lib "eagle-import") (part "BC846BW"))
    )
    (comp (ref "U35")
      (value "BC846BW")
      (footprint "eagle-import:SOT323")
      (libsource (lib "eagle-import") (part "BC846BW"))
    )
    (comp (ref "X3")
      (value "32.768KHZ")
      (footprint "eagle-import:SMD_X_2_PADS")
      (libsource (lib "eagle-import") (part "XTAL_32.768KHZ"))
    )
    (comp (ref "X4")
      (value "24MHZ")
      (footprint "eagle-import:SMD_3225")
      (libsource (lib "eagle-import") (part "XTAL_24_MHZ"))
    )
  )
  (nets
    (net (code "1") (name "C58") (class "Default")
      (node (ref "C39") (pin "P$1") (pinfunction "1_P$1") (pintype "passive"))
      (node (ref "U$2") (pin "4") (pinfunction "CT1_4") (pintype "bidirectional"))
    )
    (net (code "2") (name "C60") (class "Default")
      (node (ref "C40") (pin "P$1") (pinfunction "1_P$1") (pintype "passive"))
      (node (ref "U$2") (pin "5") (pinfunction "CT2_5") (pintype "bidirectional"))
    )
    (net (code "3") (name "CRS_DV") (class "Default")
      (node (ref "R33") (pin "P$2") (pinfunction "2_P$2") (pintype "passive"))
      (node (ref "U3") (pin "15") (pinfunction "CRS_DV/PHYAD[1:0]_15") (pintype "bidirectional"))
    )
    (net (code "4") (name "ETH") (class "Default")
      (node (ref "U3") (pin "16") (pinfunction "REF_CLK_16") (pintype "bidirectional"))
      (node (ref "U4") (pin "9") (pinfunction "P7_1_9") (pintype "bidirectional"))
    )
    (net (code "5") (name "ETH_CRS_DV") (class "Default")
      (node (ref "R33") (pin "P$1") (pinfunction "1_P$1") (pintype "passive"))
      (node (ref "U4") (pin "13") (pinfunction "P7_5_13") (pintype "bidirectional"))
    )
    (net (code "6") (name "ETH_IRQ14") (class "Default")
      (node (ref "R26") (pin "P$1") (pinfunction "1_P$1") (pintype "passive"))
      (node (ref "U3") (pin "18") (pinfunction "INTRP_18") (pintype "bidirectional"))
      (node (ref "U4") (pin "159") (pinfunction "P0_10/AN103_159") (pintype "bidirectional"))
    )
    (net (code "7") (name "ETH_MDC") (class "Default")
      (node (ref "R28") (pin "P$1") (pinfunction "1_P$1") (pintype "passive"))
      (node (ref "U3") (pin "11") (pinfunction "MDC_11") (pintype "input"))
      (node (ref "U4") (pin "4") (pinfunction "P4_3_4") (pintype "bidirectional"))
    )
    (net (code "8") (name "ETH_MDIO") (class "Default")
      (node (ref "R29") (pin "P$1") (pinfunction "1_P$1") (pintype "passive"))
      (node (ref "U3") (pin "10") (pinfunction "MDIO_10") (pintype "bidirectional"))
      (node (ref "U4") (pin "5") (pinfunction "P4_4_5") (pintype "bidirectional"))
    )
    (net (code "9") (name "ETH_RESET") (class "Default")
      (node (ref "R27") (pin "P$1") (pinfunction "1_P$1") (pintype "passive"))
      (node (ref "U$4") (pin "P$1") (pinfunction "1_P$1") (pintype "passive"))
      (node (ref "U3") (pin "24") (pinfunction "~{RST}_24") (pintype "input"))
      (node (ref "U4") (pin "172") (pinfunction "P8_6_172") (pintype "bidirectional"))
    )
    (net (code "10") (name "ETH_RXD0") (class "Default")
      (node (ref "R31") (pin "P$1") (pinfunction "1_P$1") (pintype "passive"))
      (node (ref "U4") (pin "10") (pinfunction "P7_2_10") (pintype "bidirectional"))
    )
    (net (code "11") (name "ETH_RXD1") (class "Default")
      (node (ref "R30") (pin "P$1") (pinfunction "1_P$1") (pintype "passive"))
      (node (ref "U4") (pin "11") (pinfunction "P7_3_11") (pintype "bidirectional"))
    )
    (net (code "12") (name "ETH_RX_ER") (class "Default")
      (node (ref "R32") (pin "P$1") (pinfunction "1_P$1") (pintype "passive"))
      (node (ref "U4") (pin "12") (pinfunction "P7_4_12") (pintype "bidirectional"))
    )
    (net (code "13") (name "ETH_TXD0") (class "Default")
      (node (ref "U3") (pin "20") (pinfunction "TXD0_20") (pintype "input"))
      (node (ref "U4") (pin "8") (pinfunction "P7_0_8") (pintype "bidirectional"))
    )
    (net (code "14") (name "ETH_TXD1") (class "Default")
      (node (ref "U3") (pin "21") (pinfunction "TXD1_21") (pintype "bidirectional"))
      (node (ref "U4") (pin "7") (pinfunction "P4_6_7") (pintype "bidirectional"))
    )
    (net (code "15") (name "ETH_TXD_EN") (class "Default")
      (node (ref "U3") (pin "19") (pinfunction "TXEN_19") (pintype "input"))
      (node (ref "U4") (pin "6") (pinfunction "P4_5_6") (pintype "bidirectional"))
    )
    (net (code "16") (name "F0_OUT") (class "Default")
      (node (ref "J#1") (pin "P$1") (pinfunction "P$1_P$1") (pintype "bidirectional"))
      (node (ref "J#2") (pin "P$1") (pinfunction "P$1_P$1") (pintype "bidirectional"))
      (node (ref "J#3") (pin "P$1") (pinfunction "P$1_P$1") (pintype "bidirectional"))
      (node (ref "J#7") (pin "P$1") (pinfunction "P$1_P$1") (pintype "bidirectional"))
      (node (ref "U13") (pin "3") (pinfunction "C(3)_3") (pintype "input"))
      (node (ref "U17") (pin "3") (pinfunction "C(3)_3") (pintype "input"))
      (node (ref "U33") (pin "3") (pinfunction "C(3)_3") (pintype "input"))
      (node (ref "U8") (pin "3") (pinfunction "C(3)_3") (pintype "input"))
    )
    (net (code "17") (name "F1_OUT") (class "Default")
      (node (ref "J#1") (pin "P$2") (pinfunction "P$2_P$2") (pintype "bidirectional"))
      (node (ref "J#2") (pin "P$2") (pinfunction "P$2_P$2") (pintype "bidirectional"))
      (node (ref "J#3") (pin "P$2") (pinfunction "P$2_P$2") (pintype "bidirectional"))
      (node (ref "J#7") (pin "P$2") (pinfunction "P$2_P$2") (pintype "bidirectional"))
      (node (ref "U14") (pin "3") (pinfunction "C(3)_3") (pintype "input"))
      (node (ref "U18") (pin "3") (pinfunction "C(3)_3") (pintype "input"))
      (node (ref "U34") (pin "3") (pinfunction "C(3)_3") (pintype "input"))
      (node (ref "U9") (pin "3") (pinfunction "C(3)_3") (pintype "input"))
    )
    (net (code "18") (name "F2_OUT") (class "Default")
      (node (ref "J#1") (pin "P$3") (pinfunction "P$3_P$3") (pintype "bidirectional"))
      (node (ref "J#2") (pin "P$3") (pinfunction "P$3_P$3") (pintype "bidirectional"))
      (node (ref "J#3") (pin "P$3") (pinfunction "P$3_P$3") (pintype "bidirectional"))
      (node (ref "J#7") (pin "P$3") (pinfunction "P$3_P$3") (pintype "bidirectional"))
      (node (ref "U12") (pin "3") (pinfunction "C(3)_3") (pintype "input"))
      (node (ref "U16") (pin "3") (pinfunction "C(3)_3") (pintype "input"))
      (node (ref "U32") (pin "3") (pinfunction "C(3)_3") (pintype "input"))
      (node (ref "U7") (pin "3") (pinfunction "C(3)_3") (pintype "input"))
    )
    (net (code "19") (name "F3_OUT") (class "Default")
      (node (ref "J#1") (pin "P$4") (pinfunction "P$4_P$4") (pintype "bidirectional"))
      (node (ref "J#2") (pin "P$4") (pinfunction "P$4_P$4") (pintype "bidirectional"))
      (node (ref "J#3") (pin "P$4") (pinfunction "P$4_P$4") (pintype "bidirectional"))
      (node (ref "J#7") (pin "P$4") (pinfunction "P$4_P$4") (pintype "bidirectional"))
      (node (ref "U10") (pin "3") (pinfunction "C(3)_3") (pintype "input"))
      (node (ref "U15") (pin "3") (pinfunction "C(3)_3") (pintype "input"))
      (node (ref "U19") (pin "3") (pinfunction "C(3)_3") (pintype "input"))
      (node (ref "U35") (pin "3") (pinfunction "C(3)_3") (pintype "input"))
    )
    (net (code "20") (name "GND") (class "Default")
      (node (ref "C10") (pin "P$1") (pinfunction "1_P$1") (pintype "passive"))
      (node (ref "C11") (pin "P$2") (pinfunction "2_P$2") (pintype "passive"))
      (node (ref "C13") (pin "P$1") (pinfunction "1_P$1") (pintype "passive"))
      (node (ref "C14") (pin "P$1") (pinfunction "1_P$1") (pintype "passive"))
      (node (ref "C15") (pin "2") (pinfunction "2_2") (pintype "passive"))
      (node (ref "C16") (pin "P$2") (pinfunction "2_P$2") (pintype "passive"))
      (node (ref "C30") (pin "P$1") (pinfunction "1_P$1") (pintype "passive"))
      (node (ref "C31") (pin "P$2") (pinfunction "2_P$2") (pintype "passive"))
      (node (ref "C32") (pin "P$2") (pinfunction "2_P$2") (pintype "passive"))
      (node (ref "C33") (pin "P$2") (pinfunction "2_P$2") (pintype "passive"))
      (node (ref "C34") (pin "P$2") (pinfunction "2_P$2") (pintype "passive"))
      (node (ref "C35") (pin "P$2") (pinfunction "2_P$2") (pintype "passive"))
      (node (ref "C36") (pin "P$1") (pinfunction "1_P$1") (pintype "passive"))
      (node (ref "C37") (pin "P$1") (pinfunction "1_P$1") (pintype "passive"))
      (node (ref "C38") (pin "P$2") (pinfunction "2_P$2") (pintype "passive"))
      (node (ref "C39") (pin "P$2") (pinfunction "2_P$2") (pintype "passive"))
      (node (ref "C40") (pin "P$2") (pinfunction "2_P$2") (pintype "passive"))
      (node (ref "C41") (pin "P$2") (pinfunction "2_P$2") (pintype "passive"))
      (node (ref "C42") (pin "P$2") (pinfunction "2_P$2") (pintype "passive"))
      (node (ref "C43") (pin "2") (pinfunction "2_2") (pintype "passive"))
      (node (ref "C44") (pin "P$2") (pinfunction "2_P$2") (pintype "passive"))
      (node (ref "C45") (pin "P$2") (pinfunction "2_P$2") (pintype "passive"))
      (node (ref "C46") (pin "P$2") (pinfunction "2_P$2") (pintype "passive"))
      (node (ref "C47") (pin "P$2") (pinfunction "2_P$2") (pintype "passive"))
      (node (ref "C48") (pin "2") (pinfunction "2_2") (pintype "passive"))
      (node (ref "C49") (pin "P$2") (pinfunction "2_P$2") (pintype "passive"))
      (node (ref "C5") (pin "P$2") (pinfunction "2_P$2") (pintype "passive"))
      (node (ref "C50") (pin "P$2") (pinfunction "2_P$2") (pintype "passive"))
      (node (ref "C51") (pin "P$2") (pinfunction "2_P$2") (pintype "passive"))
      (node (ref "C52") (pin "P$2") (pinfunction "2_P$2") (pintype "passive"))
      (node (ref "C53") (pin "P$2") (pinfunction "2_P$2") (pintype "passive"))
      (node (ref "C54") (pin "P$1") (pinfunction "1_P$1") (pintype "passive"))
      (node (ref "C55") (pin "P$1") (pinfunction "1_P$1") (pintype "passive"))
      (node (ref "C56") (pin "P$1") (pinfunction "1_P$1") (pintype "passive"))
      (node (ref "C57") (pin "P$2") (pinfunction "2_P$2") (pintype "passive"))
      (node (ref "C58") (pin "P$2") (pinfunction "2_P$2") (pintype "passive"))
      (node (ref "C59") (pin "P$2") (pinfunction "2_P$2") (pintype "passive"))
      (node (ref "C60") (pin "P$2") (pinfunction "2_P$2") (pintype "passive"))
      (node (ref "C61") (pin "P$1") (pinfunction "1_P$1") (pintype "passive"))
      (node (ref "C8") (pin "P$2") (pinfunction "2_P$2") (pintype "passive"))
      (node (ref "J3") (pin "GND") (pinfunction "GND_GND") (pintype "power_in"))
      (node (ref "J5") (pin "P$5") (pinfunction "GND_P$5") (pintype "bidirectional"))
      (node (ref "J6") (pin "1") (pinfunction "1_1") (pintype "passive"))
      (node (ref "J6") (pin "2") (pinfunction "2_2") (pintype "passive"))
      (node (ref "J7") (pin "10") (pinfunction "10_10") (pintype "passive"))
      (node (ref "J7") (pin "6") (pinfunction "6_6") (pintype "passive"))
      (node (ref "J7") (pin "8") (pinfunction "8_8") (pintype "passive"))
      (node (ref "J9") (pin "10") (pinfunction "10_10") (pintype "passive"))
      (node (ref "J9") (pin "2") (pinfunction "2_2") (pintype "passive"))
      (node (ref "J9") (pin "4") (pinfunction "4_4") (pintype "passive"))
      (node (ref "J9") (pin "6") (pinfunction "6_6") (pintype "passive"))
      (node (ref "J9") (pin "8") (pinfunction "8_8") (pintype "passive"))
      (node (ref "LED3") (pin "C") (pinfunction "C_C") (pintype "passive"))
      (node (ref "R16") (pin "P$1") (pinfunction "1_P$1") (pintype "passive"))
      (node (ref "R17") (pin "P$1") (pinfunction "1_P$1") (pintype "passive"))
      (node (ref "R19") (pin "P$1") (pinfunction "1_P$1") (pintype "passive"))
      (node (ref "R25") (pin "P$1") (pinfunction "1_P$1") (pintype "passive"))
      (node (ref "R7") (pin "P$1") (pinfunction "1_P$1") (pintype "passive"))
      (node (ref "U$1") (pin "P$2") (pinfunction "2_P$2") (pintype "passive"))
      (node (ref "U$10") (pin "P$2") (pinfunction "2_P$2") (pintype "passive"))
      (node (ref "U$12") (pin "P$2") (pinfunction "2_P$2") (pintype "passive"))
      (node (ref "U$13") (pin "P$2") (pinfunction "2_P$2") (pintype "passive"))
      (node (ref "U$14") (pin "P$2") (pinfunction "2_P$2") (pintype "passive"))
      (node (ref "U$15") (pin "P$2") (pinfunction "2_P$2") (pintype "passive"))
      (node (ref "U$16") (pin "P$2") (pinfunction "2_P$2") (pintype "passive"))
      (node (ref "U$17") (pin "P$2") (pinfunction "2_P$2") (pintype "passive"))
      (node (ref "U$18") (pin "P$2") (pinfunction "2_P$2") (pintype "passive"))
      (node (ref "U$2") (pin "10") (pinfunction "GLO_10") (pintype "bidirectional"))
      (node (ref "U$2") (pin "8") (pinfunction "P8_8") (pintype "bidirectional"))
      (node (ref "U$3") (pin "2") (pinfunction "2_2") (pintype "bidirectional"))
      (node (ref "U$3") (pin "4") (pinfunction "4_4") (pintype "bidirectional"))
      (node (ref "U$32") (pin "P$2") (pinfunction "2_P$2") (pintype "passive"))
      (node (ref "U$33") (pin "P$2") (pinfunction "2_P$2") (pintype "passive"))
      (node (ref "U$34") (pin "P$2") (pinfunction "2_P$2") (pintype "passive"))
      (node (ref "U$35") (pin "P$2") (pinfunction "2_P$2") (pintype "passive"))
      (node (ref "U$4") (pin "P$2") (pinfunction "2_P$2") (pintype "passive"))
      (node (ref "U$5") (pin "P$2") (pinfunction "2_P$2") (pintype "passive"))
      (node (ref "U$6") (pin "P$2") (pinfunction "2_P$2") (pintype "passive"))
      (node (ref "U$8") (pin "P$2") (pinfunction "2_P$2") (pintype "passive"))
      (node (ref "U10") (pin "2") (pinfunction "E(1)_2") (pintype "output"))
      (node (ref "U12") (pin "2") (pinfunction "E(1)_2") (pintype "output"))
      (node (ref "U13") (pin "2") (pinfunction "E(1)_2") (pintype "output"))
      (node (ref "U14") (pin "2") (pinfunction "E(1)_2") (pintype "output"))
      (node (ref "U15") (pin "2") (pinfunction "E(1)_2") (pintype "output"))
      (node (ref "U16") (pin "2") (pinfunction "E(1)_2") (pintype "output"))
      (node (ref "U17") (pin "2") (pinfunction "E(1)_2") (pintype "output"))
      (node (ref "U18") (pin "2") (pinfunction "E(1)_2") (pintype "output"))
      (node (ref "U19") (pin "2") (pinfunction "E(1)_2") (pintype "output"))
      (node (ref "U2") (pin "2") (pinfunction "GND_2") (pintype "input"))
      (node (ref "U3") (pin "22") (pinfunction "GND_22") (pintype "power_in"))
      (node (ref "U3") (pin "25") (pinfunction "25_25") (pintype "passive"))
      (node (ref "U32") (pin "2") (pinfunction "E(1)_2") (pintype "output"))
      (node (ref "U33") (pin "2") (pinfunction "E(1)_2") (pintype "output"))
      (node (ref "U34") (pin "2") (pinfunction "E(1)_2") (pintype "output"))
      (node (ref "U35") (pin "2") (pinfunction "E(1)_2") (pintype "output"))
      (node (ref "U4") (pin "111") (pinfunction "VSS(IO)5_111") (pintype "bidirectional"))
      (node (ref "U4") (pin "124") (pinfunction "VSS(IO)6_124") (pintype "bidirectional"))
      (node (ref "U4") (pin "139") (pinfunction "VSS(IO)7_139") (pintype "bidirectional"))
      (node (ref "U4") (pin "150") (pinfunction "VSS(IO)8_150") (pintype "bidirectional"))
      (node (ref "U4") (pin "156") (pinfunction "AVSS0_156") (pintype "bidirectional"))
      (node (ref "U4") (pin "170") (pinfunction "VSS(IO)9_170") (pintype "bidirectional"))
      (node (ref "U4") (pin "22") (pinfunction "VSS1_22") (pintype "bidirectional"))
      (node (ref "U4") (pin "28") (pinfunction "AVSS_USBHS_28") (pintype "bidirectional"))
      (node (ref "U4") (pin "29") (pinfunction "PVSS_USBHS_29") (pintype "bidirectional"))
      (node (ref "U4") (pin "30") (pinfunction "VSS2_USBHS_30") (pintype "bidirectional"))
      (node (ref "U4") (pin "33") (pinfunction "VSS1_USBHS_33") (pintype "bidirectional"))
      (node (ref "U4") (pin "35") (pinfunction "VSSIO_35") (pintype "bidirectional"))
      (node (ref "U4") (pin "45") (pinfunction "VSS_USB_45") (pintype "bidirectional"))
      (node (ref "U4") (pin "60") (pinfunction "VSS(IO)2_60") (pintype "bidirectional"))
      (node (ref "U4") (pin "63") (pinfunction "VSS(IO/DCDC)_63") (pintype "bidirectional"))
      (node (ref "U4") (pin "66") (pinfunction "VCC_DCDC(IO/DCDC)_66") (pintype "bidirectional"))
      (node (ref "U4") (pin "83") (pinfunction "VSS(IO)3_83") (pintype "bidirectional"))
      (node (ref "U4") (pin "98") (pinfunction "VSS(IO)4_98") (pintype "bidirectional"))
      (node (ref "U7") (pin "2") (pinfunction "E(1)_2") (pintype "output"))
      (node (ref "U8") (pin "2") (pinfunction "E(1)_2") (pintype "output"))
      (node (ref "U9") (pin "2") (pinfunction "E(1)_2") (pintype "output"))
      (node (ref "X4") (pin "2") (pinfunction "2_2") (pintype "bidirectional"))
      (node (ref "X4") (pin "4") (pinfunction "4_4") (pintype "bidirectional"))
    )
    (net (code "21") (name "GNDE") (class "Default")
      (node (ref "J3") (pin "SHLD1") (pinfunction "SHIELD_1_SHLD1") (pintype "bidirectional"))
      (node (ref "J3") (pin "SHLD2") (pinfunction "SHIELD_2_SHLD2") (pintype "bidirectional"))
      (node (ref "J5") (pin "P$6") (pinfunction "SHIELD1_P$6") (pintype "bidirectional"))
      (node (ref "J5") (pin "P$7") (pinfunction "SHIELD2_P$7") (pintype "bidirectional"))
      (node (ref "J5") (pin "P$8") (pinfunction "SHIELD3_P$8") (pintype "bidirectional"))
      (node (ref "J5") (pin "P$9") (pinfunction "SHIELD4_P$9") (pintype "bidirectional"))
      (node (ref "J6") (pin "10") (pinfunction "10_10") (pintype "passive"))
      (node (ref "J6") (pin "9") (pinfunction "9_9") (pintype "passive"))
      (node (ref "U$2") (pin "13") (pinfunction "GNDE0_13") (pintype "bidirectional"))
      (node (ref "U$2") (pin "14") (pinfunction "GNDE1_14") (pintype "bidirectional"))
    )
    (net (code "22") (name "GP4") (class "Default")
      (node (ref "U4") (pin "49") (pinfunction "P2_7_49") (pintype "bidirectional"))
    )
    (net (code "23") (name "GP21") (class "Default")
      (node (ref "U4") (pin "73") (pinfunction "P9_5_73") (pintype "bidirectional"))
    )
    (net (code "24") (name "ID") (class "Default")
      (node (ref "J5") (pin "P$4") (pinfunction "ID_P$4") (pintype "bidirectional"))
    )
    (net (code "25") (name "IIC_0_SCL") (class "Default")
      (node (ref "J11") (pin "10") (pinfunction "10_10") (pintype "passive"))
      (node (ref "R11") (pin "P$2") (pinfunction "2_P$2") (pintype "passive"))
      (node (ref "U4") (pin "1") (pinfunction "P4_0_1") (pintype "bidirectional"))
    )
    (net (code "26") (name "IIC_0_SDA") (class "Default")
      (node (ref "J11") (pin "9") (pinfunction "9_9") (pintype "passive"))
      (node (ref "R14") (pin "P$2") (pinfunction "2_P$2") (pintype "passive"))
      (node (ref "U4") (pin "2") (pinfunction "P4_1_2") (pintype "bidirectional"))
    )
    (net (code "27") (name "IIC_1_SCL") (class "Default")
      (node (ref "J8") (pin "P$5") (pinfunction "P$5_P$5") (pintype "bidirectional"))
      (node (ref "R20") (pin "P$2") (pinfunction "2_P$2") (pintype "passive"))
      (node (ref "U4") (pin "132") (pinfunction "P1_0_132") (pintype "bidirectional"))
    )
    (net (code "28") (name "IIC_1_SDA") (class "Default")
      (node (ref "J8") (pin "P$6") (pinfunction "P$6_P$6") (pintype "bidirectional"))
      (node (ref "R21") (pin "P$2") (pinfunction "2_P$2") (pintype "passive"))
      (node (ref "U4") (pin "131") (pinfunction "P1_1_131") (pintype "bidirectional"))
    )
    (net (code "29") (name "INT_AI_LS_0") (class "Default")
      (node (ref "J#5") (pin "P$1") (pinfunction "P$1_P$1") (pintype "bidirectional"))
      (node (ref "U4") (pin "3") (pinfunction "P4_2_3") (pintype "bidirectional"))
    )
    (net (code "30") (name "INT_AI_LS_1") (class "Default")
      (node (ref "J#5") (pin "P$2") (pinfunction "P$2_P$2") (pintype "bidirectional"))
      (node (ref "U4") (pin "43") (pinfunction "P4_8_43") (pintype "bidirectional"))
    )
    (net (code "31") (name "INT_AI_LS_2") (class "Default")
      (node (ref "J#5") (pin "P$3") (pinfunction "P$3_P$3") (pintype "bidirectional"))
      (node (ref "U4") (pin "53") (pinfunction "P2_3_53") (pintype "bidirectional"))
    )
    (net (code "32") (name "INT_AI_LS_3") (class "Default")
      (node (ref "J#5") (pin "P$4") (pinfunction "P$4_P$4") (pintype "bidirectional"))
      (node (ref "U4") (pin "54") (pinfunction "P2_2_54") (pintype "bidirectional"))
    )
    (net (code "33") (name "INT_MI_01") (class "Default")
      (node (ref "J8") (pin "P$39") (pinfunction "P$39_P$39") (pintype "bidirectional"))
      (node (ref "U4") (pin "87") (pinfunction "P3_1_87") (pintype "bidirectional"))
    )
    (net (code "34") (name "INT_MI_02") (class "Default")
      (node (ref "J8") (pin "P$40") (pinfunction "P$40_P$40") (pintype "bidirectional"))
      (node (ref "U4") (pin "86") (pinfunction "P3_2_86") (pintype "bidirectional"))
    )
    (net (code "35") (name "INT_MI_03") (class "Default")
      (node (ref "J8") (pin "P$9") (pinfunction "P$9_P$9") (pintype "bidirectional"))
      (node (ref "U4") (pin "128") (pinfunction "P1_4_128") (pintype "bidirectional"))
    )
    (net (code "36") (name "INT_MI_04") (class "Default")
      (node (ref "J8") (pin "P$10") (pinfunction "P$10_P$10") (pintype "bidirectional"))
      (node (ref "U4") (pin "127") (pinfunction "P1_5_127") (pintype "bidirectional"))
    )
    (net (code "37") (name "INT_MI_05") (class "Default")
      (node (ref "J8") (pin "P$1") (pinfunction "P$1_P$1") (pintype "bidirectional"))
      (node (ref "U4") (pin "141") (pinfunction "P5_1/AN116_141") (pintype "bidirectional"))
    )
    (net (code "38") (name "LED1{slash}SPEED") (class "Default")
      (node (ref "U$2") (pin "11") (pinfunction "YLO_11") (pintype "bidirectional"))
      (node (ref "U3") (pin "23") (pinfunction "LED0/ANEN_SPEED_23") (pintype "bidirectional"))
    )
    (net (code "39") (name "M0_DIR") (class "Default")
      (node (ref "RXS4") (pin "P$1") (pinfunction "1_P$1") (pintype "passive"))
      (node (ref "U4") (pin "39") (pinfunction "P4_12_39") (pintype "bidirectional"))
    )
    (net (code "40") (name "M0_STEP") (class "Default")
      (node (ref "RXS2") (pin "P$1") (pinfunction "1_P$1") (pintype "passive"))
      (node (ref "U4") (pin "16") (pinfunction "PB_0_16") (pintype "bidirectional"))
    )
    (net (code "41") (name "M1_DIR") (class "Default")
      (node (ref "RYS7") (pin "P$1") (pinfunction "1_P$1") (pintype "passive"))
      (node (ref "U4") (pin "40") (pinfunction "P4_11_40") (pintype "bidirectional"))
    )
    (net (code "42") (name "M1_STEP") (class "Default")
      (node (ref "RYS3") (pin "P$1") (pinfunction "1_P$1") (pintype "passive"))
      (node (ref "U4") (pin "36") (pinfunction "P4_15_36") (pintype "bidirectional"))
    )
    (net (code "43") (name "M2_DIR") (class "Default")
      (node (ref "RZS4") (pin "P$1") (pinfunction "1_P$1") (pintype "passive"))
      (node (ref "U4") (pin "41") (pinfunction "P4_10_41") (pintype "bidirectional"))
    )
    (net (code "44") (name "M2_STEP") (class "Default")
      (node (ref "RZS2") (pin "P$1") (pinfunction "1_P$1") (pintype "passive"))
      (node (ref "U4") (pin "37") (pinfunction "P4_14_37") (pintype "bidirectional"))
    )
    (net (code "45") (name "M3_DIR") (class "Default")
      (node (ref "RYS8") (pin "P$1") (pinfunction "1_P$1") (pintype "passive"))
      (node (ref "U4") (pin "42") (pinfunction "P4_9_42") (pintype "bidirectional"))
    )
    (net (code "46") (name "M3_STEP") (class "Default")
      (node (ref "RYS4") (pin "P$1") (pinfunction "1_P$1") (pintype "passive"))
      (node (ref "U4") (pin "38") (pinfunction "P4_13_38") (pintype "bidirectional"))
    )
    (net (code "47") (name "NC") (class "Default")
      (node (ref "U$2") (pin "7") (pinfunction "P7_7") (pintype "bidirectional"))
    )
    (net (code "48") (name "Net-(C16-1)") (class "Default")
      (node (ref "C16") (pin "P$1") (pinfunction "1_P$1") (pintype "passive"))
      (node (ref "J5") (pin "P$1") (pinfunction "VBUS_P$1") (pintype "bidirectional"))
      (node (ref "R4") (pin "P$2") (pinfunction "2_P$2") (pintype "passive"))
      (node (ref "R7") (pin "P$2") (pinfunction "2_P$2") (pintype "passive"))
    )
    (net (code "49") (name "Net-(C31-1)") (class "Default")
      (node (ref "C31") (pin "P$1") (pinfunction "1_P$1") (pintype "passive"))
      (node (ref "U4") (pin "62") (pinfunction "VCL1_62") (pintype "bidirectional"))
    )
    (net (code "50") (name "Net-(C37-2)") (class "Default")
      (node (ref "C37") (pin "P$2") (pinfunction "2_P$2") (pintype "passive"))
      (node (ref "U4") (pin "148") (pinfunction "VCL2_148") (pintype "bidirectional"))
    )
    (net (code "51") (name "Net-(C38-1)") (class "Default")
      (node (ref "C38") (pin "P$1") (pinfunction "1_P$1") (pintype "passive"))
      (node (ref "U4") (pin "19") (pinfunction "VCLO_19") (pintype "bidirectional"))
    )
    (net (code "52") (name "Net-(C44-1)") (class "Default")
      (node (ref "C43") (pin "1") (pinfunction "1_1") (pintype "passive"))
      (node (ref "C44") (pin "P$1") (pinfunction "1_P$1") (pintype "passive"))
      (node (ref "FB2/2") (pin "2") (pinfunction "P$2_2") (pintype "bidirectional"))
      (node (ref "U3") (pin "2") (pinfunction "VDDA_3.3_2") (pintype "power_in"))
    )
    (net (code "53") (name "Net-(J5-D+)") (class "Default")
      (node (ref "J5") (pin "P$3") (pinfunction "D+_P$3") (pintype "bidirectional"))
      (node (ref "R6") (pin "P$2") (pinfunction "2_P$2") (pintype "passive"))
    )
    (net (code "54") (name "Net-(J5-D-)") (class "Default")
      (node (ref "J5") (pin "P$2") (pinfunction "D-_P$2") (pintype "bidirectional"))
      (node (ref "R5") (pin "P$2") (pinfunction "2_P$2") (pintype "passive"))
    )
    (net (code "55") (name "Net-(R13-1)") (class "Default")
      (node (ref "LED3") (pin "A") (pinfunction "A_A") (pintype "passive"))
      (node (ref "R13") (pin "P$1") (pinfunction "1_P$1") (pintype "passive"))
    )
    (net (code "56") (name "Net-(R16-2)") (class "Default")
      (node (ref "R16") (pin "P$2") (pinfunction "2_P$2") (pintype "passive"))
      (node (ref "U4") (pin "65") (pinfunction "VLO2(DCDC)_65") (pintype "bidirectional"))
    )
    (net (code "57") (name "Net-(R17-2)") (class "Default")
      (node (ref "R17") (pin "P$2") (pinfunction "2_P$2") (pintype "passive"))
      (node (ref "U4") (pin "64") (pinfunction "VLO1(DCDC)_64") (pintype "bidirectional"))
    )
    (net (code "58") (name "Net-(R19-2)") (class "Default")
      (node (ref "R19") (pin "P$2") (pinfunction "2_P$2") (pintype "passive"))
      (node (ref "U4") (pin "27") (pinfunction "USBHS_RREF_27") (pintype "bidirectional"))
    )
    (net (code "59") (name "Net-(RXS2-2)") (class "Default")
      (node (ref "RXS2") (pin "P$2") (pinfunction "2_P$2") (pintype "passive"))
      (node (ref "U$5") (pin "P$1") (pinfunction "1_P$1") (pintype "passive"))
      (node (ref "U8") (pin "1") (pinfunction "B(2)_1") (pintype "input"))
    )
    (net (code "60") (name "Net-(RXS3-2)") (class "Default")
      (node (ref "RXS3") (pin "P$2") (pinfunction "2_P$2") (pintype "passive"))
      (node (ref "U$12") (pin "P$1") (pinfunction "1_P$1") (pintype "passive"))
      (node (ref "U13") (pin "1") (pinfunction "B(2)_1") (pintype "input"))
    )
    (net (code "61") (name "Net-(RXS4-2)") (class "Default")
      (node (ref "RXS4") (pin "P$2") (pinfunction "2_P$2") (pintype "passive"))
      (node (ref "U$16") (pin "P$1") (pinfunction "1_P$1") (pintype "passive"))
      (node (ref "U17") (pin "1") (pinfunction "B(2)_1") (pintype "input"))
    )
    (net (code "62") (name "Net-(RXS8-2)") (class "Default")
      (node (ref "RXS8") (pin "P$2") (pinfunction "2_P$2") (pintype "passive"))
      (node (ref "U$33") (pin "P$1") (pinfunction "1_P$1") (pintype "passive"))
      (node (ref "U33") (pin "1") (pinfunction "B(2)_1") (pintype "input"))
    )
    (net (code "63") (name "Net-(RYS3-2)") (class "Default")
      (node (ref "RYS3") (pin "P$2") (pinfunction "2_P$2") (pintype "passive"))
      (node (ref "U$6") (pin "P$1") (pinfunction "1_P$1") (pintype "passive"))
      (node (ref "U9") (pin "1") (pinfunction "B(2)_1") (pintype "input"))
    )
    (net (code "64") (name "Net-(RYS4-2)") (class "Default")
      (node (ref "RYS4") (pin "P$2") (pinfunction "2_P$2") (pintype "passive"))
      (node (ref "U$8") (pin "P$1") (pinfunction "1_P$1") (pintype "passive"))
      (node (ref "U10") (pin "1") (pinfunction "B(2)_1") (pintype "input"))
    )
    (net (code "65") (name "Net-(RYS5-2)") (class "Default")
      (node (ref "RYS5") (pin "P$2") (pinfunction "2_P$2") (pintype "passive"))
      (node (ref "U$13") (pin "P$1") (pinfunction "1_P$1") (pintype "passive"))
      (node (ref "U14") (pin "1") (pinfunction "B(2)_1") (pintype "input"))
    )
    (net (code "66") (name "Net-(RYS6-2)") (class "Default")
      (node (ref "RYS6") (pin "P$2") (pinfunction "2_P$2") (pintype "passive"))
      (node (ref "U$14") (pin "P$1") (pinfunction "1_P$1") (pintype "passive"))
      (node (ref "U15") (pin "1") (pinfunction "B(2)_1") (pintype "input"))
    )
    (net (code "67") (name "Net-(RYS7-2)") (class "Default")
      (node (ref "RYS7") (pin "P$2") (pinfunction "2_P$2") (pintype "passive"))
      (node (ref "U$17") (pin "P$1") (pinfunction "1_P$1") (pintype "passive"))
      (node (ref "U18") (pin "1") (pinfunction "B(2)_1") (pintype "input"))
    )
    (net (code "68") (name "Net-(RYS8-2)") (class "Default")
      (node (ref "RYS8") (pin "P$2") (pinfunction "2_P$2") (pintype "passive"))
      (node (ref "U$18") (pin "P$1") (pinfunction "1_P$1") (pintype "passive"))
      (node (ref "U19") (pin "1") (pinfunction "B(2)_1") (pintype "input"))
    )
    (net (code "69") (name "Net-(RYS15-2)") (class "Default")
      (node (ref "RYS15") (pin "P$2") (pinfunction "2_P$2") (pintype "passive"))
      (node (ref "U$34") (pin "P$1") (pinfunction "1_P$1") (pintype "passive"))
      (node (ref "U34") (pin "1") (pinfunction "B(2)_1") (pintype "input"))
    )
    (net (code "70") (name "Net-(RYS16-2)") (class "Default")
      (node (ref "RYS16") (pin "P$2") (pinfunction "2_P$2") (pintype "passive"))
      (node (ref "U$35") (pin "P$1") (pinfunction "1_P$1") (pintype "passive"))
      (node (ref "U35") (pin "1") (pinfunction "B(2)_1") (pintype "input"))
    )
    (net (code "71") (name "Net-(RZS2-2)") (class "Default")
      (node (ref "RZS2") (pin "P$2") (pinfunction "2_P$2") (pintype "passive"))
      (node (ref "U$1") (pin "P$1") (pinfunction "1_P$1") (pintype "passive"))
      (node (ref "U7") (pin "1") (pinfunction "B(2)_1") (pintype "input"))
    )
    (net (code "72") (name "Net-(RZS3-2)") (class "Default")
      (node (ref "RZS3") (pin "P$2") (pinfunction "2_P$2") (pintype "passive"))
      (node (ref "U$10") (pin "P$1") (pinfunction "1_P$1") (pintype "passive"))
      (node (ref "U12") (pin "1") (pinfunction "B(2)_1") (pintype "input"))
    )
    (net (code "73") (name "Net-(RZS4-2)") (class "Default")
      (node (ref "RZS4") (pin "P$2") (pinfunction "2_P$2") (pintype "passive"))
      (node (ref "U$15") (pin "P$1") (pinfunction "1_P$1") (pintype "passive"))
      (node (ref "U16") (pin "1") (pinfunction "B(2)_1") (pintype "input"))
    )
    (net (code "74") (name "Net-(RZS8-2)") (class "Default")
      (node (ref "RZS8") (pin "P$2") (pinfunction "2_P$2") (pintype "passive"))
      (node (ref "U$32") (pin "P$1") (pinfunction "1_P$1") (pintype "passive"))
      (node (ref "U32") (pin "1") (pinfunction "B(2)_1") (pintype "input"))
    )
    (net (code "75") (name "P0_00") (class "Default")
      (node (ref "J11") (pin "3") (pinfunction "3_3") (pintype "passive"))
      (node (ref "U4") (pin "169") (pinfunction "P0_0/AN0\\00_169") (pintype "bidirectional"))
    )
    (net (code "76") (name "P0_01") (class "Default")
      (node (ref "J11") (pin "4") (pinfunction "4_4") (pintype "passive"))
      (node (ref "U4") (pin "168") (pinfunction "P0_1/AN001_168") (pintype "bidirectional"))
    )
    (net (code "77") (name "P0_02") (class "Default")
      (node (ref "J11") (pin "1") (pinfunction "1_1") (pintype "passive"))
      (node (ref "U4") (pin "167") (pinfunction "P0_2/AN002_167") (pintype "bidirectional"))
    )
    (net (code "78") (name "P0_03") (class "Default")
      (node (ref "J11") (pin "2") (pinfunction "2_2") (pintype "passive"))
      (node (ref "U4") (pin "166") (pinfunction "P0_3/PGAVSS000_166") (pintype "bidirectional"))
    )
    (net (code "79") (name "P0_04") (class "Default")
      (node (ref "J14") (pin "9") (pinfunction "9_9") (pintype "passive"))
      (node (ref "U4") (pin "165") (pinfunction "P0_4/AN100_165") (pintype "bidirectional"))
    )
    (net (code "80") (name "P0_05") (class "Default")
      (node (ref "J14") (pin "10") (pinfunction "10_10") (pintype "passive"))
      (node (ref "U4") (pin "164") (pinfunction "P0_5/AN101_164") (pintype "bidirectional"))
    )
    (net (code "81") (name "P0_06") (class "Default")
      (node (ref "J14") (pin "7") (pinfunction "7_7") (pintype "passive"))
      (node (ref "U4") (pin "163") (pinfunction "P0_6/AN102_163") (pintype "bidirectional"))
    )
    (net (code "82") (name "P0_07") (class "Default")
      (node (ref "J14") (pin "8") (pinfunction "8_8") (pintype "passive"))
      (node (ref "U4") (pin "162") (pinfunction "P0_7/PGVSS100_162") (pintype "bidirectional"))
    )
    (net (code "83") (name "P0_08") (class "Default")
      (node (ref "J14") (pin "5") (pinfunction "5_5") (pintype "passive"))
      (node (ref "U4") (pin "161") (pinfunction "P0_8/AN003_161") (pintype "bidirectional"))
    )
    (net (code "84") (name "P0_09") (class "Default")
      (node (ref "J14") (pin "6") (pinfunction "6_6") (pintype "passive"))
      (node (ref "U4") (pin "160") (pinfunction "P0_9/AN004_160") (pintype "bidirectional"))
    )
    (net (code "85") (name "P0_14") (class "Default")
      (node (ref "J14") (pin "3") (pinfunction "3_3") (pintype "passive"))
      (node (ref "U4") (pin "152") (pinfunction "P0_14/DA0/AN005/AN105_152") (pintype "bidirectional"))
    )
    (net (code "86") (name "P0_15") (class "Default")
      (node (ref "J14") (pin "4") (pinfunction "4_4") (pintype "passive"))
      (node (ref "U4") (pin "151") (pinfunction "P0_15/DA1/AN006/AN106_151") (pintype "bidirectional"))
    )
    (net (code "87") (name "P1_02") (class "Default")
      (node (ref "J8") (pin "P$7") (pinfunction "P$7_P$7") (pintype "bidirectional"))
      (node (ref "U4") (pin "130") (pinfunction "P1_2_130") (pintype "bidirectional"))
    )
    (net (code "88") (name "P1_03") (class "Default")
      (node (ref "J8") (pin "P$8") (pinfunction "P$8_P$8") (pintype "bidirectional"))
      (node (ref "U4") (pin "129") (pinfunction "P1_3_129") (pintype "bidirectional"))
    )
    (net (code "89") (name "P1_06") (class "Default")
      (node (ref "J8") (pin "P$11") (pinfunction "P$11_P$11") (pintype "bidirectional"))
      (node (ref "U4") (pin "126") (pinfunction "P1_6_126") (pintype "bidirectional"))
    )
    (net (code "90") (name "P1_07") (class "Default")
      (node (ref "J8") (pin "P$12") (pinfunction "P$12_P$12") (pintype "bidirectional"))
      (node (ref "U4") (pin "125") (pinfunction "P1_7_125") (pintype "bidirectional"))
    )
    (net (code "91") (name "P1_11") (class "Default")
      (node (ref "J8") (pin "P$38") (pinfunction "P$38_P$38") (pintype "bidirectional"))
      (node (ref "U4") (pin "92") (pinfunction "P1_11_92") (pintype "bidirectional"))
    )
    (net (code "92") (name "P1_12") (class "Default")
      (node (ref "J8") (pin "P$37") (pinfunction "P$37_P$37") (pintype "bidirectional"))
      (node (ref "U4") (pin "93") (pinfunction "P1_12_93") (pintype "bidirectional"))
    )
    (net (code "93") (name "P1_13") (class "Default")
      (node (ref "J8") (pin "P$36") (pinfunction "P$36_P$36") (pintype "bidirectional"))
      (node (ref "U4") (pin "94") (pinfunction "P1_13_94") (pintype "bidirectional"))
    )
    (net (code "94") (name "P1_14") (class "Default")
      (node (ref "J8") (pin "P$35") (pinfunction "P$35_P$35") (pintype "bidirectional"))
      (node (ref "U4") (pin "95") (pinfunction "P1_14_95") (pintype "bidirectional"))
    )
    (net (code "95") (name "P1_15") (class "Default")
      (node (ref "J8") (pin "P$34") (pinfunction "P$34_P$34") (pintype "bidirectional"))
      (node (ref "U4") (pin "96") (pinfunction "P1_15_96") (pintype "bidirectional"))
    )
    (net (code "96") (name "P2_00") (class "Default")
      (node (ref "J9") (pin "3") (pinfunction "3_3") (pintype "passive"))
      (node (ref "R3") (pin "P$2") (pinfunction "2_P$2") (pintype "passive"))
      (node (ref "U4") (pin "69") (pinfunction "P2_0(INPUT_ONLY)_69") (pintype "bidirectional"))
    )
    (net (code "97") (name "P2_01") (class "Default")
      (node (ref "J9") (pin "1") (pinfunction "1_1") (pintype "passive"))
      (node (ref "R2") (pin "P$2") (pinfunction "2_P$2") (pintype "passive"))
      (node (ref "U4") (pin "68") (pinfunction "P2_1/MD_68") (pintype "bidirectional"))
    )
    (net (code "98") (name "P3_03") (class "Default")
      (node (ref "J10") (pin "1") (pinfunction "1_1") (pintype "passive"))
      (node (ref "U4") (pin "85") (pinfunction "P3_3_85") (pintype "bidirectional"))
    )
    (net (code "99") (name "P3_04") (class "Default")
      (node (ref "J10") (pin "2") (pinfunction "2_2") (pintype "passive"))
      (node (ref "U4") (pin "82") (pinfunction "P3_4_82") (pintype "bidirectional"))
    )
    (net (code "100") (name "P3_05") (class "Default")
      (node (ref "J10") (pin "3") (pinfunction "3_3") (pintype "passive"))
      (node (ref "U4") (pin "81") (pinfunction "P3_5_81") (pintype "bidirectional"))
    )
    (net (code "101") (name "P3_06") (class "Default")
      (node (ref "J10") (pin "4") (pinfunction "4_4") (pintype "passive"))
      (node (ref "U4") (pin "80") (pinfunction "P3_6_80") (pintype "bidirectional"))
    )
    (net (code "102") (name "P3_07") (class "Default")
      (node (ref "J10") (pin "5") (pinfunction "5_5") (pintype "passive"))
      (node (ref "U4") (pin "79") (pinfunction "P3_7_79") (pintype "bidirectional"))
    )
    (net (code "103") (name "P3_09") (class "Default")
      (node (ref "J10") (pin "6") (pinfunction "6_6") (pintype "passive"))
      (node (ref "U4") (pin "77") (pinfunction "P3_9_77") (pintype "bidirectional"))
    )
    (net (code "104") (name "P3_10") (class "Default")
      (node (ref "J10") (pin "7") (pinfunction "7_7") (pintype "passive"))
      (node (ref "U4") (pin "76") (pinfunction "P3_10_76") (pintype "bidirectional"))
    )
    (net (code "105") (name "P3_11") (class "Default")
      (node (ref "J10") (pin "8") (pinfunction "8_8") (pintype "passive"))
      (node (ref "U4") (pin "75") (pinfunction "P3_11_75") (pintype "bidirectional"))
    )
    (net (code "106") (name "P3_12") (class "Default")
      (node (ref "J10") (pin "9") (pinfunction "9_9") (pintype "passive"))
      (node (ref "U4") (pin "74") (pinfunction "P3_12_74") (pintype "bidirectional"))
    )
    (net (code "107") (name "P5_00") (class "Default")
      (node (ref "U4") (pin "140") (pinfunction "P5_0/AN016_140") (pintype "bidirectional"))
    )
    (net (code "108") (name "P5_02") (class "Default")
      (node (ref "U4") (pin "142") (pinfunction "P5_2/AN017_142") (pintype "bidirectional"))
    )
    (net (code "109") (name "P5_03") (class "Default")
      (node (ref "U4") (pin "143") (pinfunction "P5_3/AN117_143") (pintype "bidirectional"))
    )
    (net (code "110") (name "P5_04") (class "Default")
      (node (ref "U4") (pin "144") (pinfunction "P5_4/AN018_144") (pintype "bidirectional"))
    )
    (net (code "111") (name "P5_05") (class "Default")
      (node (ref "U4") (pin "145") (pinfunction "P5_5/AN118_145") (pintype "bidirectional"))
    )
    (net (code "112") (name "P5_06") (class "Default")
      (node (ref "U4") (pin "146") (pinfunction "P5_6/AN019_146") (pintype "bidirectional"))
    )
    (net (code "113") (name "P5_07") (class "Default")
      (node (ref "U4") (pin "147") (pinfunction "P5_7/AN119_147") (pintype "bidirectional"))
    )
    (net (code "114") (name "P5_11") (class "Default")
      (node (ref "J11") (pin "7") (pinfunction "7_7") (pintype "passive"))
      (node (ref "U4") (pin "176") (pinfunction "P5_11_176") (pintype "bidirectional"))
    )
    (net (code "115") (name "P5_12") (class "Default")
      (node (ref "J11") (pin "8") (pinfunction "8_8") (pintype "passive"))
      (node (ref "U4") (pin "175") (pinfunction "P5_12_175") (pintype "bidirectional"))
    )
    (net (code "116") (name "P5_13") (class "Default")
      (node (ref "J11") (pin "5") (pinfunction "5_5") (pintype "passive"))
      (node (ref "U4") (pin "174") (pinfunction "P5_13_174") (pintype "bidirectional"))
    )
    (net (code "117") (name "P6_00") (class "Default")
      (node (ref "J8") (pin "P$13") (pinfunction "P$13_P$13") (pintype "bidirectional"))
      (node (ref "U4") (pin "122") (pinfunction "P6_0_122") (pintype "bidirectional"))
    )
    (net (code "118") (name "P6_01") (class "Default")
      (node (ref "J8") (pin "P$14") (pinfunction "P$14_P$14") (pintype "bidirectional"))
      (node (ref "U4") (pin "121") (pinfunction "P6_1_121") (pintype "bidirectional"))
    )
    (net (code "119") (name "P6_02") (class "Default")
      (node (ref "J8") (pin "P$15") (pinfunction "P$15_P$15") (pintype "bidirectional"))
      (node (ref "U4") (pin "120") (pinfunction "P6_2_120") (pintype "bidirectional"))
    )
    (net (code "120") (name "P6_03") (class "Default")
      (node (ref "J8") (pin "P$16") (pinfunction "P$16_P$16") (pintype "bidirectional"))
      (node (ref "U4") (pin "119") (pinfunction "P6_3_119") (pintype "bidirectional"))
    )
    (net (code "121") (name "P6_04") (class "Default")
      (node (ref "J8") (pin "P$17") (pinfunction "P$17_P$17") (pintype "bidirectional"))
      (node (ref "U4") (pin "118") (pinfunction "P6_4_118") (pintype "bidirectional"))
    )
    (net (code "122") (name "P6_05") (class "Default")
      (node (ref "J8") (pin "P$18") (pinfunction "P$18_P$18") (pintype "bidirectional"))
      (node (ref "U4") (pin "117") (pinfunction "P6_5_117") (pintype "bidirectional"))
    )
    (net (code "123") (name "P6_06") (class "Default")
      (node (ref "J8") (pin "P$19") (pinfunction "P$19_P$19") (pintype "bidirectional"))
      (node (ref "U4") (pin "116") (pinfunction "P6_6_116") (pintype "bidirectional"))
    )
    (net (code "124") (name "P6_07") (class "Default")
      (node (ref "J8") (pin "P$20") (pinfunction "P$20_P$20") (pintype "bidirectional"))
      (node (ref "U4") (pin "115") (pinfunction "P6_7_115") (pintype "bidirectional"))
    )
    (net (code "125") (name "P6_08") (class "Default")
      (node (ref "J8") (pin "P$33") (pinfunction "P$33_P$33") (pintype "bidirectional"))
      (node (ref "U4") (pin "99") (pinfunction "P6_8_99") (pintype "bidirectional"))
    )
    (net (code "126") (name "P6_09") (class "Default")
      (node (ref "J8") (pin "P$32") (pinfunction "P$32_P$32") (pintype "bidirectional"))
      (node (ref "U4") (pin "100") (pinfunction "P6_9_100") (pintype "bidirectional"))
    )
    (net (code "127") (name "P6_10") (class "Default")
      (node (ref "J8") (pin "P$31") (pinfunction "P$31_P$31") (pintype "bidirectional"))
      (node (ref "U4") (pin "101") (pinfunction "P6_10_101") (pintype "bidirectional"))
    )
    (net (code "128") (name "P6_11") (class "Default")
      (node (ref "J8") (pin "P$30") (pinfunction "P$30_P$30") (pintype "bidirectional"))
      (node (ref "U4") (pin "102") (pinfunction "P6_11_102") (pintype "bidirectional"))
    )
    (net (code "129") (name "P6_12") (class "Default")
      (node (ref "J8") (pin "P$29") (pinfunction "P$29_P$29") (pintype "bidirectional"))
      (node (ref "U4") (pin "103") (pinfunction "P6_12_103") (pintype "bidirectional"))
    )
    (net (code "130") (name "P6_13") (class "Default")
      (node (ref "J8") (pin "P$28") (pinfunction "P$28_P$28") (pintype "bidirectional"))
      (node (ref "U4") (pin "104") (pinfunction "P6_13_104") (pintype "bidirectional"))
    )
    (net (code "131") (name "P6_14") (class "Default")
      (node (ref "J8") (pin "P$27") (pinfunction "P$27_P$27") (pintype "bidirectional"))
      (node (ref "U4") (pin "105") (pinfunction "P6_14_105") (pintype "bidirectional"))
    )
    (net (code "132") (name "P6_15") (class "Default")
      (node (ref "J8") (pin "P$26") (pinfunction "P$26_P$26") (pintype "bidirectional"))
      (node (ref "U4") (pin "106") (pinfunction "P6_15_106") (pintype "bidirectional"))
    )
    (net (code "133") (name "P7_06") (class "Default")
      (node (ref "U4") (pin "14") (pinfunction "P7_6_14") (pintype "bidirectional"))
    )
    (net (code "134") (name "P7_07") (class "Default")
      (node (ref "U4") (pin "15") (pinfunction "P7_7_15") (pintype "bidirectional"))
    )
    (net (code "135") (name "P8_00") (class "Default")
      (node (ref "J8") (pin "P$4") (pinfunction "P$4_P$4") (pintype "bidirectional"))
      (node (ref "U4") (pin "133") (pinfunction "P8_0_133") (pintype "bidirectional"))
    )
    (net (code "136") (name "P8_01") (class "Default")
      (node (ref "J8") (pin "P$3") (pinfunction "P$3_P$3") (pintype "bidirectional"))
      (node (ref "U4") (pin "134") (pinfunction "P8_1_134") (pintype "bidirectional"))
    )
    (net (code "137") (name "P8_02") (class "Default")
      (node (ref "J8") (pin "P$2") (pinfunction "P$2_P$2") (pintype "bidirectional"))
      (node (ref "U4") (pin "135") (pinfunction "P8_2_135") (pintype "bidirectional"))
    )
    (net (code "138") (name "P8_03") (class "Default")
      (node (ref "J14") (pin "2") (pinfunction "2_2") (pintype "passive"))
      (node (ref "U4") (pin "136") (pinfunction "P8_3_136") (pintype "bidirectional"))
    )
    (net (code "139") (name "P8_04") (class "Default")
      (node (ref "J14") (pin "1") (pinfunction "1_1") (pintype "passive"))
      (node (ref "U4") (pin "137") (pinfunction "P8_4_137") (pintype "bidirectional"))
    )
    (net (code "140") (name "P8_05") (class "Default")
      (node (ref "J11") (pin "6") (pinfunction "6_6") (pintype "passive"))
      (node (ref "U4") (pin "173") (pinfunction "P8_5_173") (pintype "bidirectional"))
    )
    (net (code "141") (name "P9_05") (class "Default")
      (node (ref "J10") (pin "10") (pinfunction "10_10") (pintype "passive"))
    )
    (net (code "142") (name "P9_06") (class "Default")
      (node (ref "J9") (pin "9") (pinfunction "9_9") (pintype "passive"))
      (node (ref "R10") (pin "P$2") (pinfunction "2_P$2") (pintype "passive"))
      (node (ref "U4") (pin "72") (pinfunction "P9_6_72") (pintype "bidirectional"))
    )
    (net (code "143") (name "P9_07") (class "Default")
      (node (ref "J9") (pin "7") (pinfunction "7_7") (pintype "passive"))
      (node (ref "R9") (pin "P$2") (pinfunction "2_P$2") (pintype "passive"))
      (node (ref "U4") (pin "71") (pinfunction "P9_7_71") (pintype "bidirectional"))
    )
    (net (code "144") (name "P9_08") (class "Default")
      (node (ref "J9") (pin "5") (pinfunction "5_5") (pintype "passive"))
      (node (ref "R8") (pin "P$2") (pinfunction "2_P$2") (pintype "passive"))
      (node (ref "U4") (pin "70") (pinfunction "P9_8_70") (pintype "bidirectional"))
    )
    (net (code "145") (name "PA_00") (class "Default")
      (node (ref "J8") (pin "P$21") (pinfunction "P$21_P$21") (pintype "bidirectional"))
      (node (ref "U4") (pin "114") (pinfunction "PA_0_114") (pintype "bidirectional"))
    )
    (net (code "146") (name "PA_01") (class "Default")
      (node (ref "J8") (pin "P$22") (pinfunction "P$22_P$22") (pintype "bidirectional"))
      (node (ref "U4") (pin "113") (pinfunction "PA_1_113") (pintype "bidirectional"))
    )
    (net (code "147") (name "PA_08") (class "Default")
      (node (ref "J8") (pin "P$25") (pinfunction "P$25_P$25") (pintype "bidirectional"))
      (node (ref "U4") (pin "107") (pinfunction "PA_8_107") (pintype "bidirectional"))
    )
    (net (code "148") (name "PA_09") (class "Default")
      (node (ref "J8") (pin "P$24") (pinfunction "P$24_P$24") (pintype "bidirectional"))
      (node (ref "U4") (pin "108") (pinfunction "PA_9_108") (pintype "bidirectional"))
    )
    (net (code "149") (name "PA_10") (class "Default")
      (node (ref "J8") (pin "P$23") (pinfunction "P$23_P$23") (pintype "bidirectional"))
      (node (ref "U4") (pin "109") (pinfunction "PA_10_109") (pintype "bidirectional"))
    )
    (net (code "150") (name "R51") (class "Default")
      (node (ref "R23") (pin "P$1") (pinfunction "1_P$1") (pintype "passive"))
      (node (ref "U$2") (pin "12") (pinfunction "YHI_12") (pintype "bidirectional"))
    )
    (net (code "151") (name "R52") (class "Default")
      (node (ref "R24") (pin "P$1") (pinfunction "1_P$1") (pintype "passive"))
      (node (ref "U$2") (pin "9") (pinfunction "GHI_9") (pintype "bidirectional"))
    )
    (net (code "152") (name "RELAY_0") (class "Default")
      (node (ref "RYS6") (pin "P$1") (pinfunction "1_P$1") (pintype "passive"))
      (node (ref "U4") (pin "59") (pinfunction "P9_1_59") (pintype "bidirectional"))
    )
    (net (code "153") (name "RELAY_1") (class "Default")
      (node (ref "RZS3") (pin "P$1") (pinfunction "1_P$1") (pintype "passive"))
      (node (ref "U4") (pin "58") (pinfunction "P9_0_58") (pintype "bidirectional"))
    )
    (net (code "154") (name "RELAY_2") (class "Default")
      (node (ref "RYS5") (pin "P$1") (pinfunction "1_P$1") (pintype "passive"))
      (node (ref "U4") (pin "57") (pinfunction "P3_15_57") (pintype "bidirectional"))
    )
    (net (code "155") (name "RELAY_3") (class "Default")
      (node (ref "RXS3") (pin "P$1") (pinfunction "1_P$1") (pintype "passive"))
      (node (ref "U4") (pin "56") (pinfunction "P3_14_56") (pintype "bidirectional"))
    )
    (net (code "156") (name "RELAY_4") (class "Default")
      (node (ref "RYS16") (pin "P$1") (pinfunction "1_P$1") (pintype "passive"))
      (node (ref "U4") (pin "55") (pinfunction "P3_13_55") (pintype "bidirectional"))
    )
    (net (code "157") (name "RELAY_5") (class "Default")
      (node (ref "RZS8") (pin "P$1") (pinfunction "1_P$1") (pintype "passive"))
      (node (ref "U4") (pin "52") (pinfunction "P2_4_52") (pintype "bidirectional"))
    )
    (net (code "158") (name "RELAY_6") (class "Default")
      (node (ref "RYS15") (pin "P$1") (pinfunction "1_P$1") (pintype "passive"))
      (node (ref "U4") (pin "51") (pinfunction "P2_5_51") (pintype "bidirectional"))
    )
    (net (code "159") (name "RELAY_7") (class "Default")
      (node (ref "RXS8") (pin "P$1") (pinfunction "1_P$1") (pintype "passive"))
      (node (ref "U4") (pin "50") (pinfunction "P2_6_50") (pintype "bidirectional"))
    )
    (net (code "160") (name "RESET") (class "Default")
      (node (ref "C57") (pin "P$1") (pinfunction "1_P$1") (pintype "passive"))
      (node (ref "J7") (pin "9") (pinfunction "9_9") (pintype "passive"))
      (node (ref "R18") (pin "P$1") (pinfunction "1_P$1") (pintype "passive"))
      (node (ref "U4") (pin "67") (pinfunction "RES#_67") (pintype "bidirectional"))
    )
    (net (code "161") (name "REXT") (class "Default")
      (node (ref "C47") (pin "P$1") (pinfunction "1_P$1") (pintype "passive"))
      (node (ref "R25") (pin "P$2") (pinfunction "2_P$2") (pintype "passive"))
      (node (ref "U3") (pin "9") (pinfunction "REXT_9") (pintype "input"))
    )
    (net (code "162") (name "RXD0") (class "Default")
      (node (ref "R31") (pin "P$2") (pinfunction "2_P$2") (pintype "passive"))
      (node (ref "U3") (pin "13") (pinfunction "RXD0_13") (pintype "bidirectional"))
    )
    (net (code "163") (name "RXD1") (class "Default")
      (node (ref "R30") (pin "P$2") (pinfunction "2_P$2") (pintype "passive"))
      (node (ref "U3") (pin "12") (pinfunction "RXD1_12") (pintype "bidirectional"))
    )
    (net (code "164") (name "RXER") (class "Default")
      (node (ref "R32") (pin "P$2") (pinfunction "2_P$2") (pintype "passive"))
      (node (ref "U3") (pin "17") (pinfunction "RXER_17") (pintype "bidirectional"))
    )
    (net (code "165") (name "RXM") (class "Default")
      (node (ref "U$2") (pin "6") (pinfunction "RD-_6") (pintype "bidirectional"))
      (node (ref "U3") (pin "3") (pinfunction "RXM_3") (pintype "bidirectional"))
    )
    (net (code "166") (name "RXP") (class "Default")
      (node (ref "U$2") (pin "3") (pinfunction "RD+_3") (pintype "bidirectional"))
      (node (ref "U3") (pin "4") (pinfunction "RXP_4") (pintype "bidirectional"))
    )
    (net (code "167") (name "TCK") (class "Default")
      (node (ref "J7") (pin "7") (pinfunction "7_7") (pintype "passive"))
      (node (ref "U4") (pin "88") (pinfunction "P3_0_88") (pintype "bidirectional"))
    )
    (net (code "168") (name "TDI") (class "Default")
      (node (ref "J7") (pin "1") (pinfunction "1_1") (pintype "passive"))
      (node (ref "U4") (pin "91") (pinfunction "P1_10_91") (pintype "bidirectional"))
    )
    (net (code "169") (name "TDO") (class "Default")
      (node (ref "J7") (pin "3") (pinfunction "3_3") (pintype "passive"))
      (node (ref "U4") (pin "90") (pinfunction "P1_9_90") (pintype "bidirectional"))
    )
    (net (code "170") (name "TMS") (class "Default")
      (node (ref "J7") (pin "5") (pinfunction "5_5") (pintype "passive"))
      (node (ref "U4") (pin "89") (pinfunction "P1_8_89") (pintype "bidirectional"))
    )
    (net (code "171") (name "TXM") (class "Default")
      (node (ref "U$2") (pin "2") (pinfunction "TD-_2") (pintype "bidirectional"))
      (node (ref "U3") (pin "5") (pinfunction "TXM_5") (pintype "bidirectional"))
    )
    (net (code "172") (name "TXP") (class "Default")
      (node (ref "U$2") (pin "1") (pinfunction "TD+_1") (pintype "bidirectional"))
      (node (ref "U3") (pin "6") (pinfunction "TXP_6") (pintype "bidirectional"))
    )
    (net (code "173") (name "USBHS_FAULT") (class "Default")
      (node (ref "R12") (pin "P$1") (pinfunction "1_P$1") (pintype "passive"))
      (node (ref "U2") (pin "3") (pinfunction "FLG_3") (pintype "input"))
      (node (ref "U4") (pin "78") (pinfunction "P3_8_78") (pintype "bidirectional"))
    )
    (net (code "174") (name "USBHS_N") (class "Default")
      (node (ref "J3") (pin "D-") (pinfunction "D-_D-") (pintype "bidirectional"))
      (node (ref "U4") (pin "31") (pinfunction "USBHS_DM_31") (pintype "bidirectional"))
    )
    (net (code "175") (name "USBHS_P") (class "Default")
      (node (ref "J3") (pin "D+") (pinfunction "D+_D+") (pintype "bidirectional"))
      (node (ref "U4") (pin "32") (pinfunction "USBHS_DP_32") (pintype "bidirectional"))
    )
    (net (code "176") (name "USBHS_VBUS") (class "Default")
      (node (ref "C11") (pin "P$1") (pinfunction "1_P$1") (pintype "passive"))
      (node (ref "C15") (pin "1") (pinfunction "1_1") (pintype "passive"))
      (node (ref "J3") (pin "VBUS") (pinfunction "VBUS_VBUS") (pintype "power_in"))
      (node (ref "U2") (pin "5") (pinfunction "OUT_5") (pintype "input"))
      (node (ref "U4") (pin "17") (pinfunction "PB_1_17") (pintype "bidirectional"))
    )
    (net (code "177") (name "USBHS_VBUSEN") (class "Default")
      (node (ref "R1") (pin "P$1") (pinfunction "1_P$1") (pintype "passive"))
      (node (ref "U2") (pin "1") (pinfunction "EN_1") (pintype "input"))
    )
    (net (code "178") (name "USB_N") (class "Default")
      (node (ref "R5") (pin "P$1") (pinfunction "1_P$1") (pintype "passive"))
      (node (ref "U4") (pin "46") (pinfunction "USB_DM_46") (pintype "bidirectional"))
    )
    (net (code "179") (name "USB_P") (class "Default")
      (node (ref "R6") (pin "P$1") (pinfunction "1_P$1") (pintype "passive"))
      (node (ref "U4") (pin "47") (pinfunction "USB_DP_47") (pintype "bidirectional"))
    )
    (net (code "180") (name "USB_VBUS_B") (class "Default")
      (node (ref "R4") (pin "P$1") (pinfunction "1_P$1") (pintype "passive"))
      (node (ref "U4") (pin "44") (pinfunction "P4_7_44") (pintype "bidirectional"))
    )
    (net (code "181") (name "VCL_F(FLASH)") (class "Default")
      (node (ref "C36") (pin "P$2") (pinfunction "2_P$2") (pintype "passive"))
      (node (ref "U4") (pin "112") (pinfunction "VCL_F(FLASH)_112") (pintype "bidirectional"))
    )
    (net (code "182") (name "VDD") (class "Default")
      (node (ref "C10") (pin "P$2") (pinfunction "2_P$2") (pintype "passive"))
      (node (ref "C13") (pin "P$2") (pinfunction "2_P$2") (pintype "passive"))
      (node (ref "C14") (pin "P$2") (pinfunction "2_P$2") (pintype "passive"))
      (node (ref "C30") (pin "P$2") (pinfunction "2_P$2") (pintype "passive"))
      (node (ref "C32") (pin "P$1") (pinfunction "1_P$1") (pintype "passive"))
      (node (ref "C33") (pin "P$1") (pinfunction "1_P$1") (pintype "passive"))
      (node (ref "C34") (pin "P$1") (pinfunction "1_P$1") (pintype "passive"))
      (node (ref "C35") (pin "P$1") (pinfunction "1_P$1") (pintype "passive"))
      (node (ref "C48") (pin "1") (pinfunction "1_1") (pintype "passive"))
      (node (ref "C49") (pin "P$1") (pinfunction "1_P$1") (pintype "passive"))
      (node (ref "C54") (pin "P$2") (pinfunction "2_P$2") (pintype "passive"))
      (node (ref "C55") (pin "P$2") (pinfunction "2_P$2") (pintype "passive"))
      (node (ref "C56") (pin "P$2") (pinfunction "2_P$2") (pintype "passive"))
      (node (ref "C58") (pin "P$1") (pinfunction "1_P$1") (pintype "passive"))
      (node (ref "C59") (pin "P$1") (pinfunction "1_P$1") (pintype "passive"))
      (node (ref "C60") (pin "P$1") (pinfunction "1_P$1") (pintype "passive"))
      (node (ref "C61") (pin "P$2") (pinfunction "2_P$2") (pintype "passive"))
      (node (ref "FB2/2") (pin "1") (pinfunction "P$1_1") (pintype "bidirectional"))
      (node (ref "J7") (pin "2") (pinfunction "2_2") (pintype "passive"))
      (node (ref "J7") (pin "4") (pinfunction "4_4") (pintype "passive"))
      (node (ref "L3") (pin "2") (pinfunction "P$2_2") (pintype "bidirectional"))
      (node (ref "R10") (pin "P$1") (pinfunction "1_P$1") (pintype "passive"))
      (node (ref "R11") (pin "P$1") (pinfunction "1_P$1") (pintype "passive"))
      (node (ref "R13") (pin "P$2") (pinfunction "2_P$2") (pintype "passive"))
      (node (ref "R14") (pin "P$1") (pinfunction "1_P$1") (pintype "passive"))
      (node (ref "R18") (pin "P$2") (pinfunction "2_P$2") (pintype "passive"))
      (node (ref "R2") (pin "P$1") (pinfunction "1_P$1") (pintype "passive"))
      (node (ref "R20") (pin "P$1") (pinfunction "1_P$1") (pintype "passive"))
      (node (ref "R21") (pin "P$1") (pinfunction "1_P$1") (pintype "passive"))
      (node (ref "R23") (pin "P$2") (pinfunction "2_P$2") (pintype "passive"))
      (node (ref "R24") (pin "P$2") (pinfunction "2_P$2") (pintype "passive"))
      (node (ref "R26") (pin "P$2") (pinfunction "2_P$2") (pintype "passive"))
      (node (ref "R27") (pin "P$2") (pinfunction "2_P$2") (pintype "passive"))
      (node (ref "R28") (pin "P$2") (pinfunction "2_P$2") (pintype "passive"))
      (node (ref "R29") (pin "P$2") (pinfunction "2_P$2") (pintype "passive"))
      (node (ref "R3") (pin "P$1") (pinfunction "1_P$1") (pintype "passive"))
      (node (ref "R8") (pin "P$1") (pinfunction "1_P$1") (pintype "passive"))
      (node (ref "R9") (pin "P$1") (pinfunction "1_P$1") (pintype "passive"))
      (node (ref "U3") (pin "14") (pinfunction "VDDIO_14") (pintype "power_in"))
      (node (ref "U4") (pin "110") (pinfunction "VCC(IO)5_110") (pintype "bidirectional"))
      (node (ref "U4") (pin "123") (pinfunction "VCC(IO)6_123") (pintype "bidirectional"))
      (node (ref "U4") (pin "138") (pinfunction "VCC(IO)7_138") (pintype "bidirectional"))
      (node (ref "U4") (pin "149") (pinfunction "VCC(IO)8_149") (pintype "bidirectional"))
      (node (ref "U4") (pin "155") (pinfunction "AVCC0_155") (pintype "bidirectional"))
      (node (ref "U4") (pin "171") (pinfunction "VCC(IO)9_171") (pintype "bidirectional"))
      (node (ref "U4") (pin "25") (pinfunction "VCC1_25") (pintype "bidirectional"))
      (node (ref "U4") (pin "26") (pinfunction "AVCC_SUBHS_26") (pintype "bidirectional"))
      (node (ref "U4") (pin "34") (pinfunction "VCC_USBHS_34") (pintype "bidirectional"))
      (node (ref "U4") (pin "48") (pinfunction "VCC_USB_48") (pintype "bidirectional"))
      (node (ref "U4") (pin "61") (pinfunction "VCC(IO)2_61") (pintype "bidirectional"))
      (node (ref "U4") (pin "84") (pinfunction "VCC(IO)3_84") (pintype "bidirectional"))
      (node (ref "U4") (pin "97") (pinfunction "VCC(IO)4_97") (pintype "bidirectional"))
    )
    (net (code "183") (name "VDD5") (class "Default")
      (node (ref "C5") (pin "P$1") (pinfunction "1_P$1") (pintype "passive"))
      (node (ref "C8") (pin "P$1") (pinfunction "1_P$1") (pintype "passive"))
      (node (ref "J6") (pin "5") (pinfunction "5_5") (pintype "passive"))
      (node (ref "J6") (pin "6") (pinfunction "6_6") (pintype "passive"))
      (node (ref "R1") (pin "P$2") (pinfunction "2_P$2") (pintype "passive"))
      (node (ref "R12") (pin "P$2") (pinfunction "2_P$2") (pintype "passive"))
      (node (ref "U2") (pin "4") (pinfunction "VIN_4") (pintype "input"))
    )
    (net (code "184") (name "VDD12") (class "Default")
      (node (ref "J6") (pin "7") (pinfunction "7_7") (pintype "passive"))
      (node (ref "J6") (pin "8") (pinfunction "8_8") (pintype "passive"))
    )
    (net (code "185") (name "VDDIN") (class "Default")
      (node (ref "J6") (pin "3") (pinfunction "3_3") (pintype "passive"))
      (node (ref "J6") (pin "4") (pinfunction "4_4") (pintype "passive"))
      (node (ref "L3") (pin "1") (pinfunction "P$1_1") (pintype "bidirectional"))
    )
    (net (code "186") (name "VDD_1.2") (class "Default")
      (node (ref "C45") (pin "P$1") (pinfunction "1_P$1") (pintype "passive"))
      (node (ref "C46") (pin "P$1") (pinfunction "1_P$1") (pintype "passive"))
      (node (ref "U3") (pin "1") (pinfunction "VDD_1.2_1") (pintype "power_in"))
    )
    (net (code "187") (name "XCIN") (class "Default")
      (node (ref "C50") (pin "P$1") (pinfunction "1_P$1") (pintype "passive"))
      (node (ref "U4") (pin "20") (pinfunction "XCIN_20") (pintype "bidirectional"))
      (node (ref "X3") (pin "P$1") (pinfunction "P$1_P$1") (pintype "bidirectional"))
    )
    (net (code "188") (name "XCOUT") (class "Default")
      (node (ref "C51") (pin "P$1") (pinfunction "1_P$1") (pintype "passive"))
      (node (ref "U4") (pin "21") (pinfunction "XCOUT_21") (pintype "bidirectional"))
      (node (ref "X3") (pin "P$2") (pinfunction "P$2_P$2") (pintype "bidirectional"))
    )
    (net (code "189") (name "XII") (class "Default")
      (node (ref "C42") (pin "P$1") (pinfunction "1_P$1") (pintype "passive"))
      (node (ref "U$3") (pin "1") (pinfunction "1_1") (pintype "bidirectional"))
      (node (ref "U3") (pin "8") (pinfunction "XI_8") (pintype "input"))
    )
    (net (code "190") (name "XOO") (class "Default")
      (node (ref "C41") (pin "P$1") (pinfunction "1_P$1") (pintype "passive"))
      (node (ref "U$3") (pin "3") (pinfunction "3_3") (pintype "bidirectional"))
      (node (ref "U3") (pin "7") (pinfunction "XO_7") (pintype "output"))
    )
    (net (code "191") (name "XTAL1") (class "Default")
      (node (ref "C52") (pin "P$1") (pinfunction "1_P$1") (pintype "passive"))
      (node (ref "U4") (pin "23") (pinfunction "P2_13/XTAL_23") (pintype "bidirectional"))
      (node (ref "X4") (pin "1") (pinfunction "1_1") (pintype "bidirectional"))
    )
    (net (code "192") (name "XTAL2") (class "Default")
      (node (ref "C53") (pin "P$1") (pinfunction "1_P$1") (pintype "passive"))
      (node (ref "U4") (pin "24") (pinfunction "P2_12/EXTAL_24") (pintype "bidirectional"))
      (node (ref "X4") (pin "3") (pinfunction "3_3") (pintype "bidirectional"))
    )
    (net (code "193") (name "unconnected-(U4-VBAT-Pad18)") (class "Default")
      (node (ref "U4") (pin "18") (pinfunction "VBAT_18") (pintype "bidirectional"))
    )
    (net (code "194") (name "unconnected-(U4-VREFH-Pad154)") (class "Default")
      (node (ref "U4") (pin "154") (pinfunction "VREFH_154") (pintype "bidirectional"))
    )
    (net (code "195") (name "unconnected-(U4-VREFH0-Pad158)") (class "Default")
      (node (ref "U4") (pin "158") (pinfunction "VREFH0_158") (pintype "bidirectional"))
    )
    (net (code "196") (name "unconnected-(U4-VREFL-Pad153)") (class "Default")
      (node (ref "U4") (pin "153") (pinfunction "VREFL_153") (pintype "bidirectional"))
    )
    (net (code "197") (name "unconnected-(U4-VREFL0-Pad157)") (class "Default")
      (node (ref "U4") (pin "157") (pinfunction "VREFL0_157") (pintype "bidirectional"))
    )
  )
)
